# HOL-Dash_1_2.net
KiCad netlist of a schematic drawn in Altium Designer
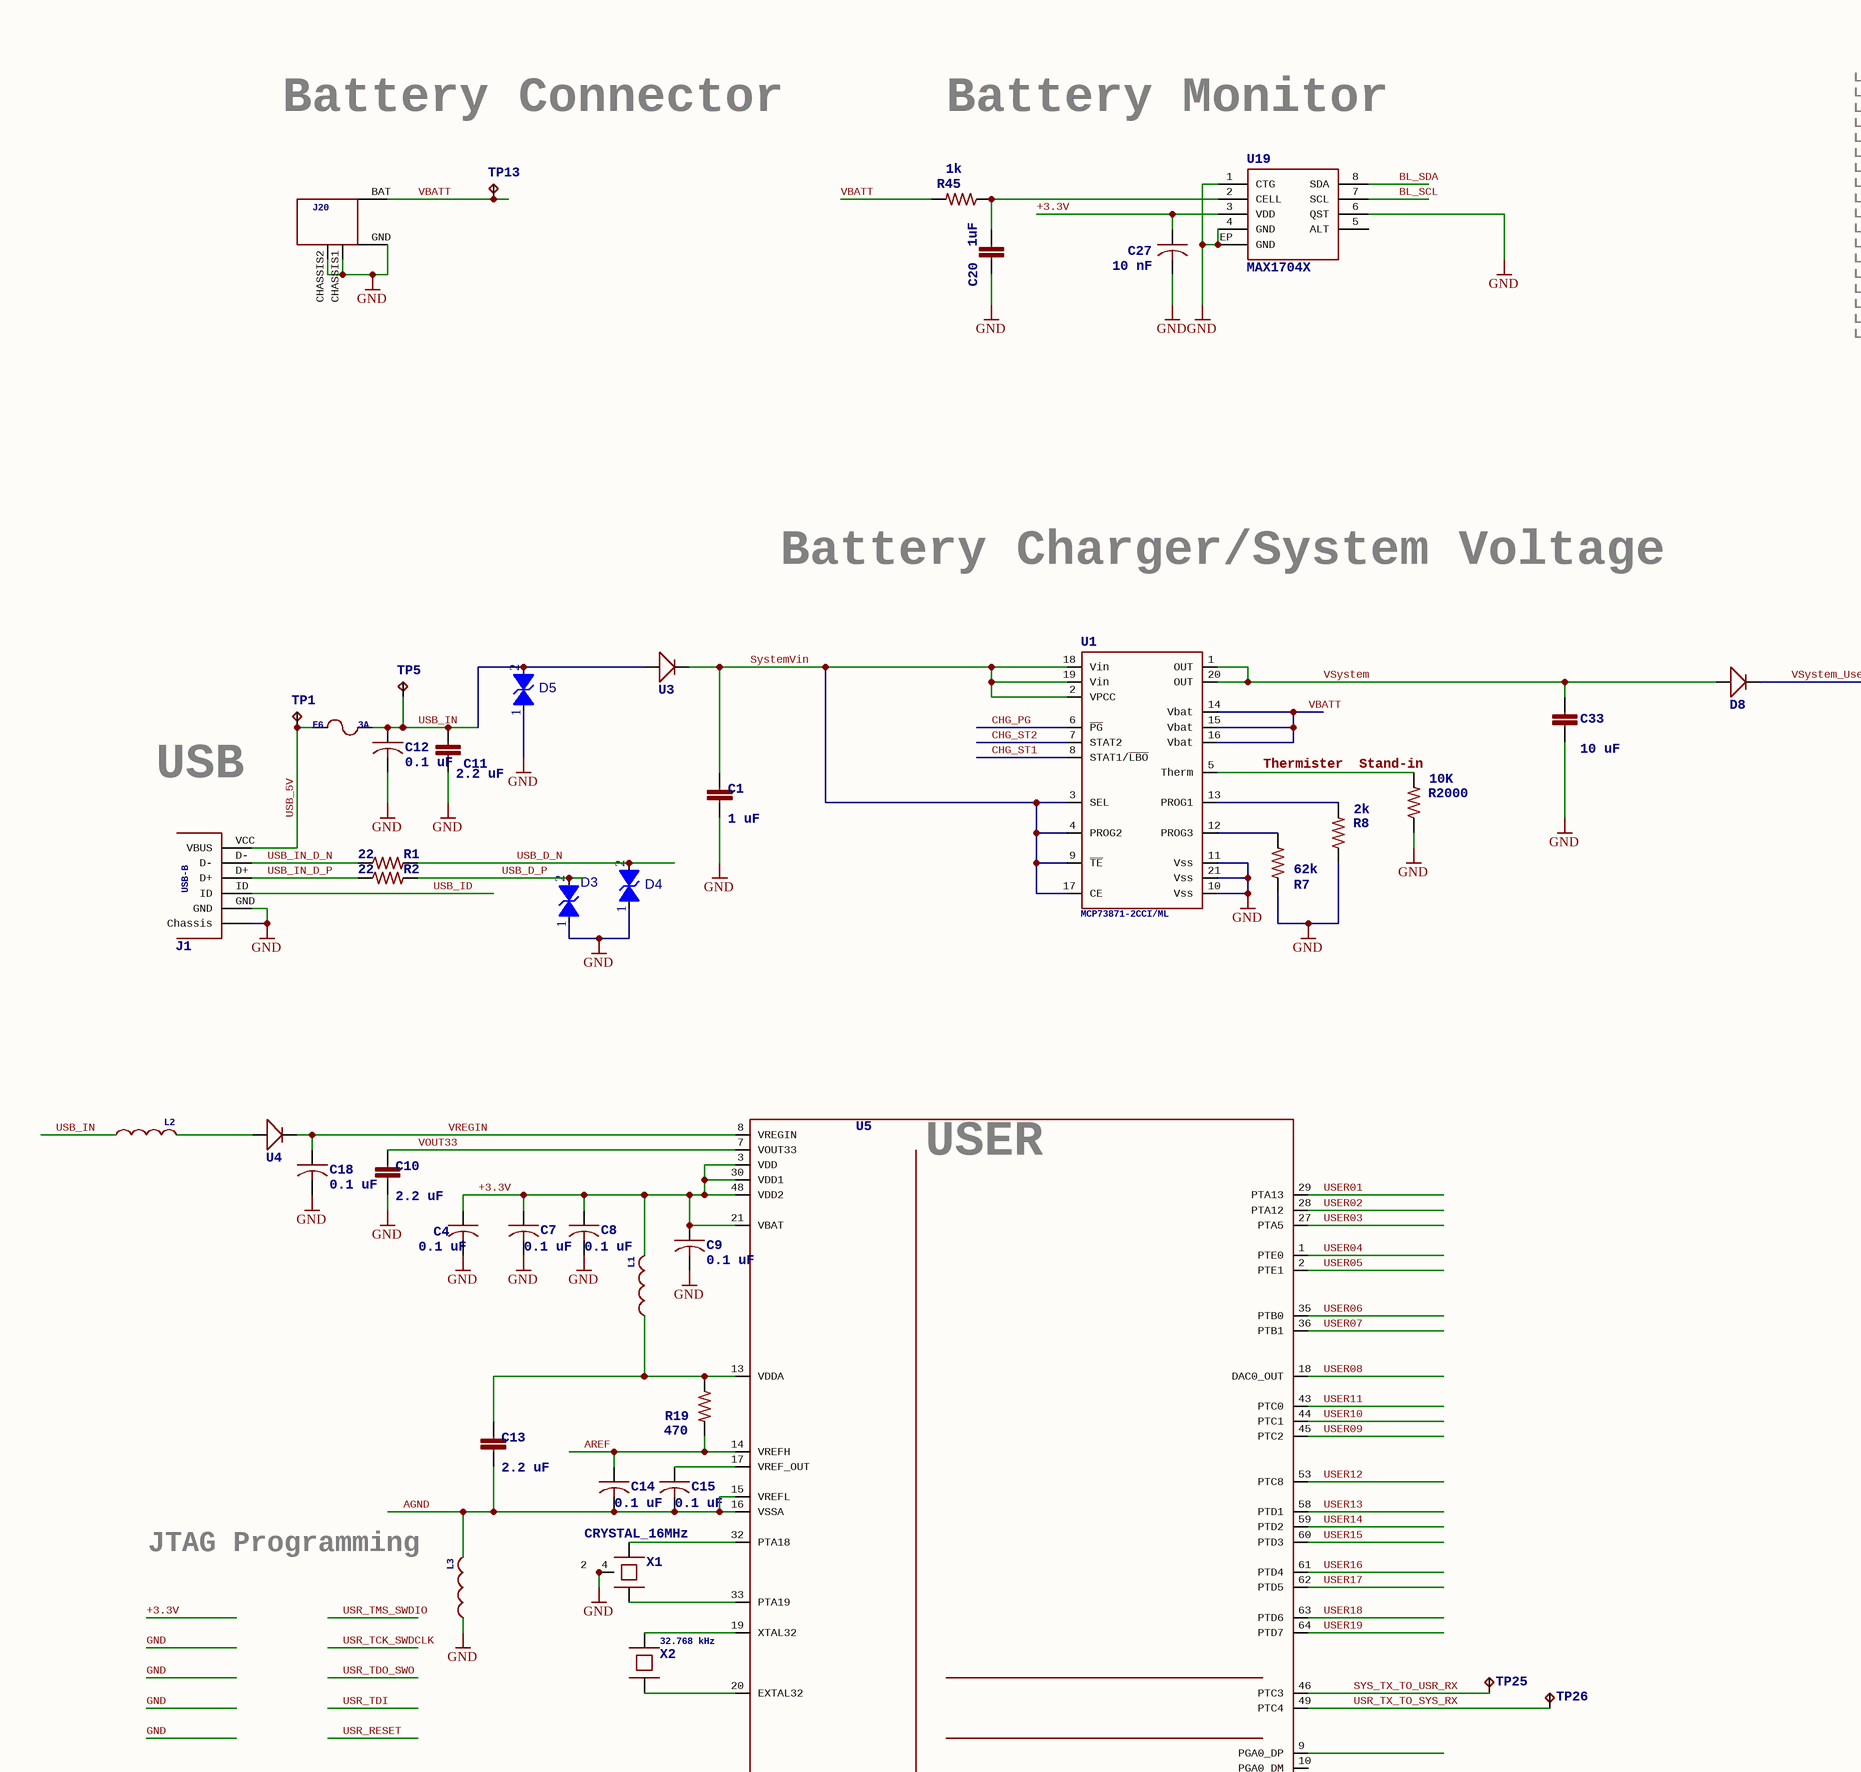
[diagram p0: HOL-Dash_1_2.SchDoc, top left]
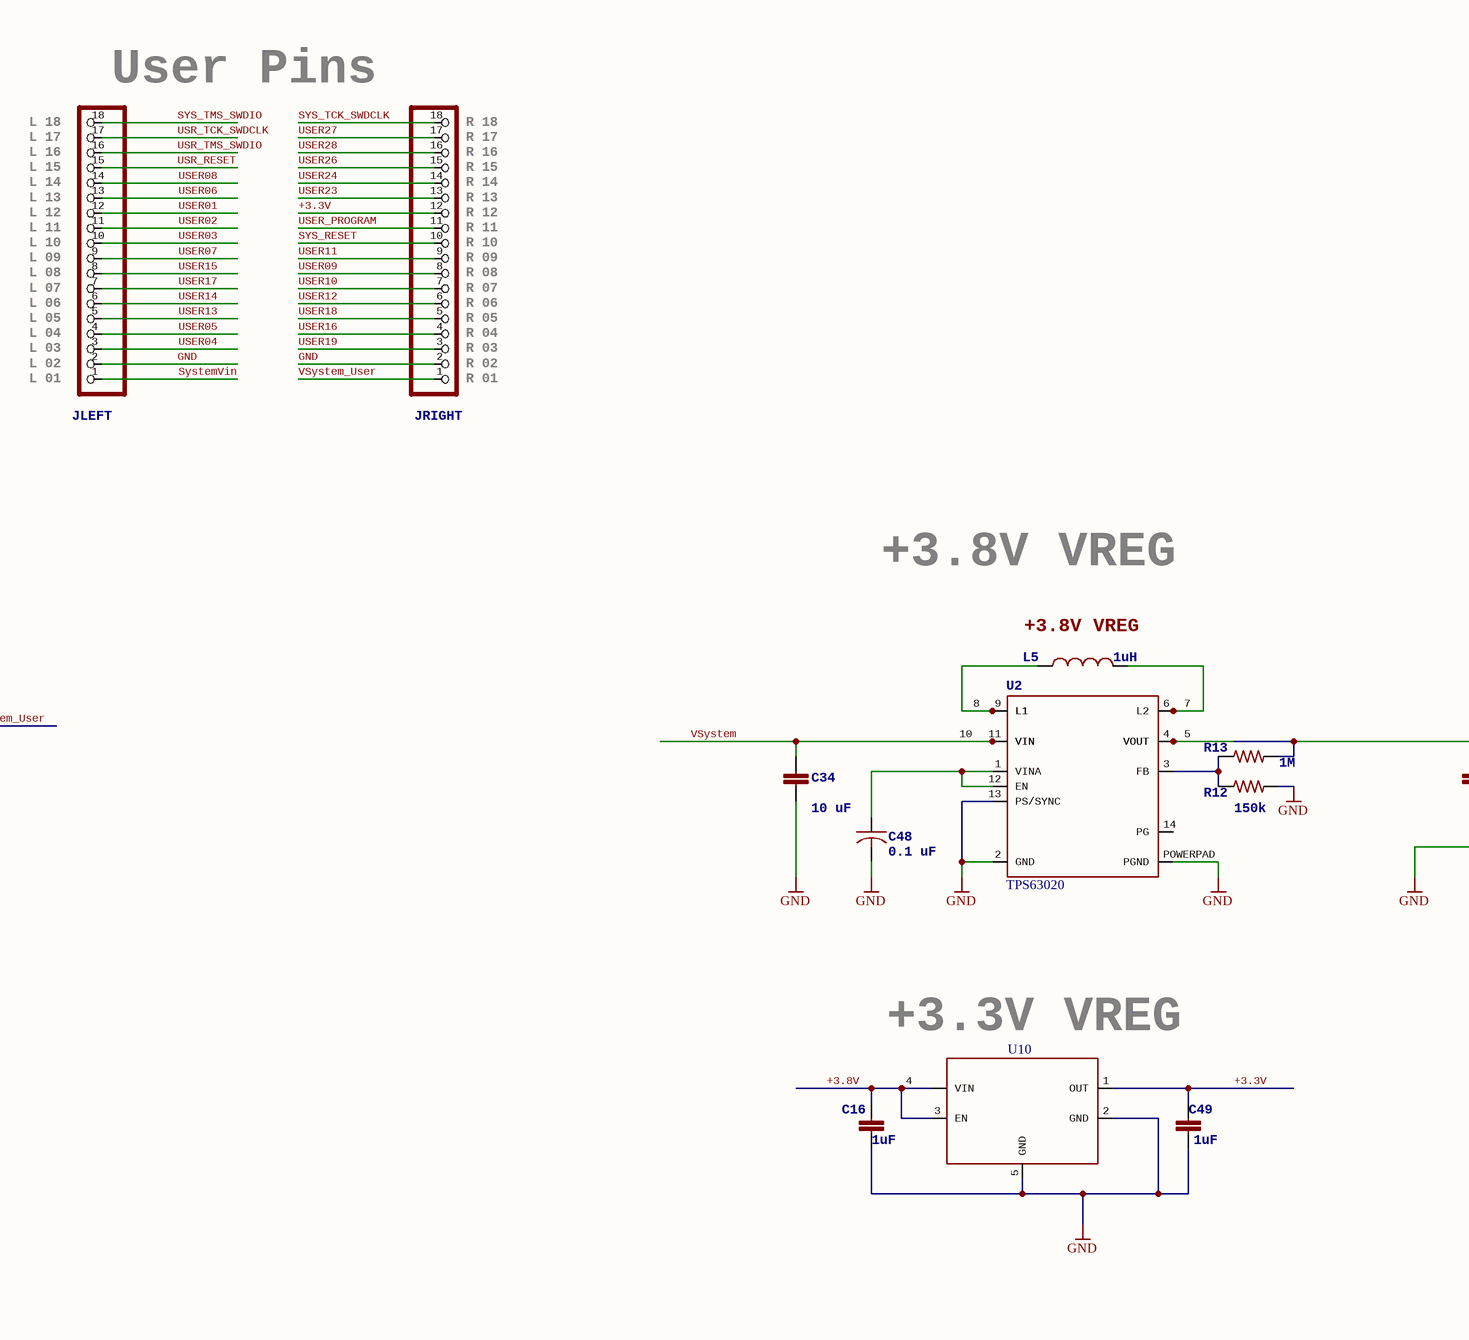
[diagram p1: HOL-Dash_1_2.SchDoc, top middle]
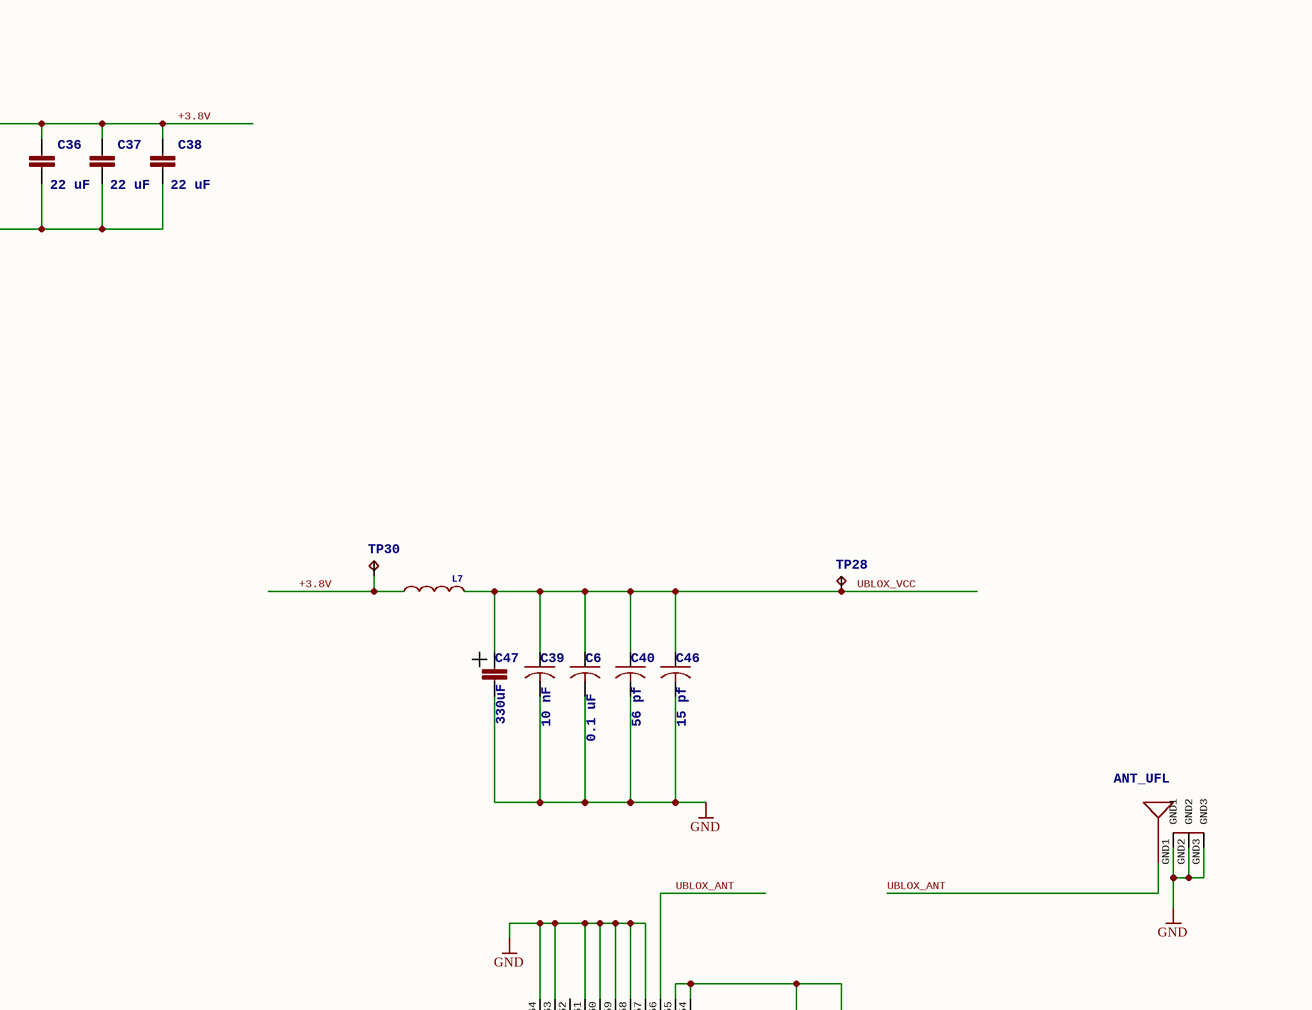
[diagram p2: HOL-Dash_1_2.SchDoc, top right]
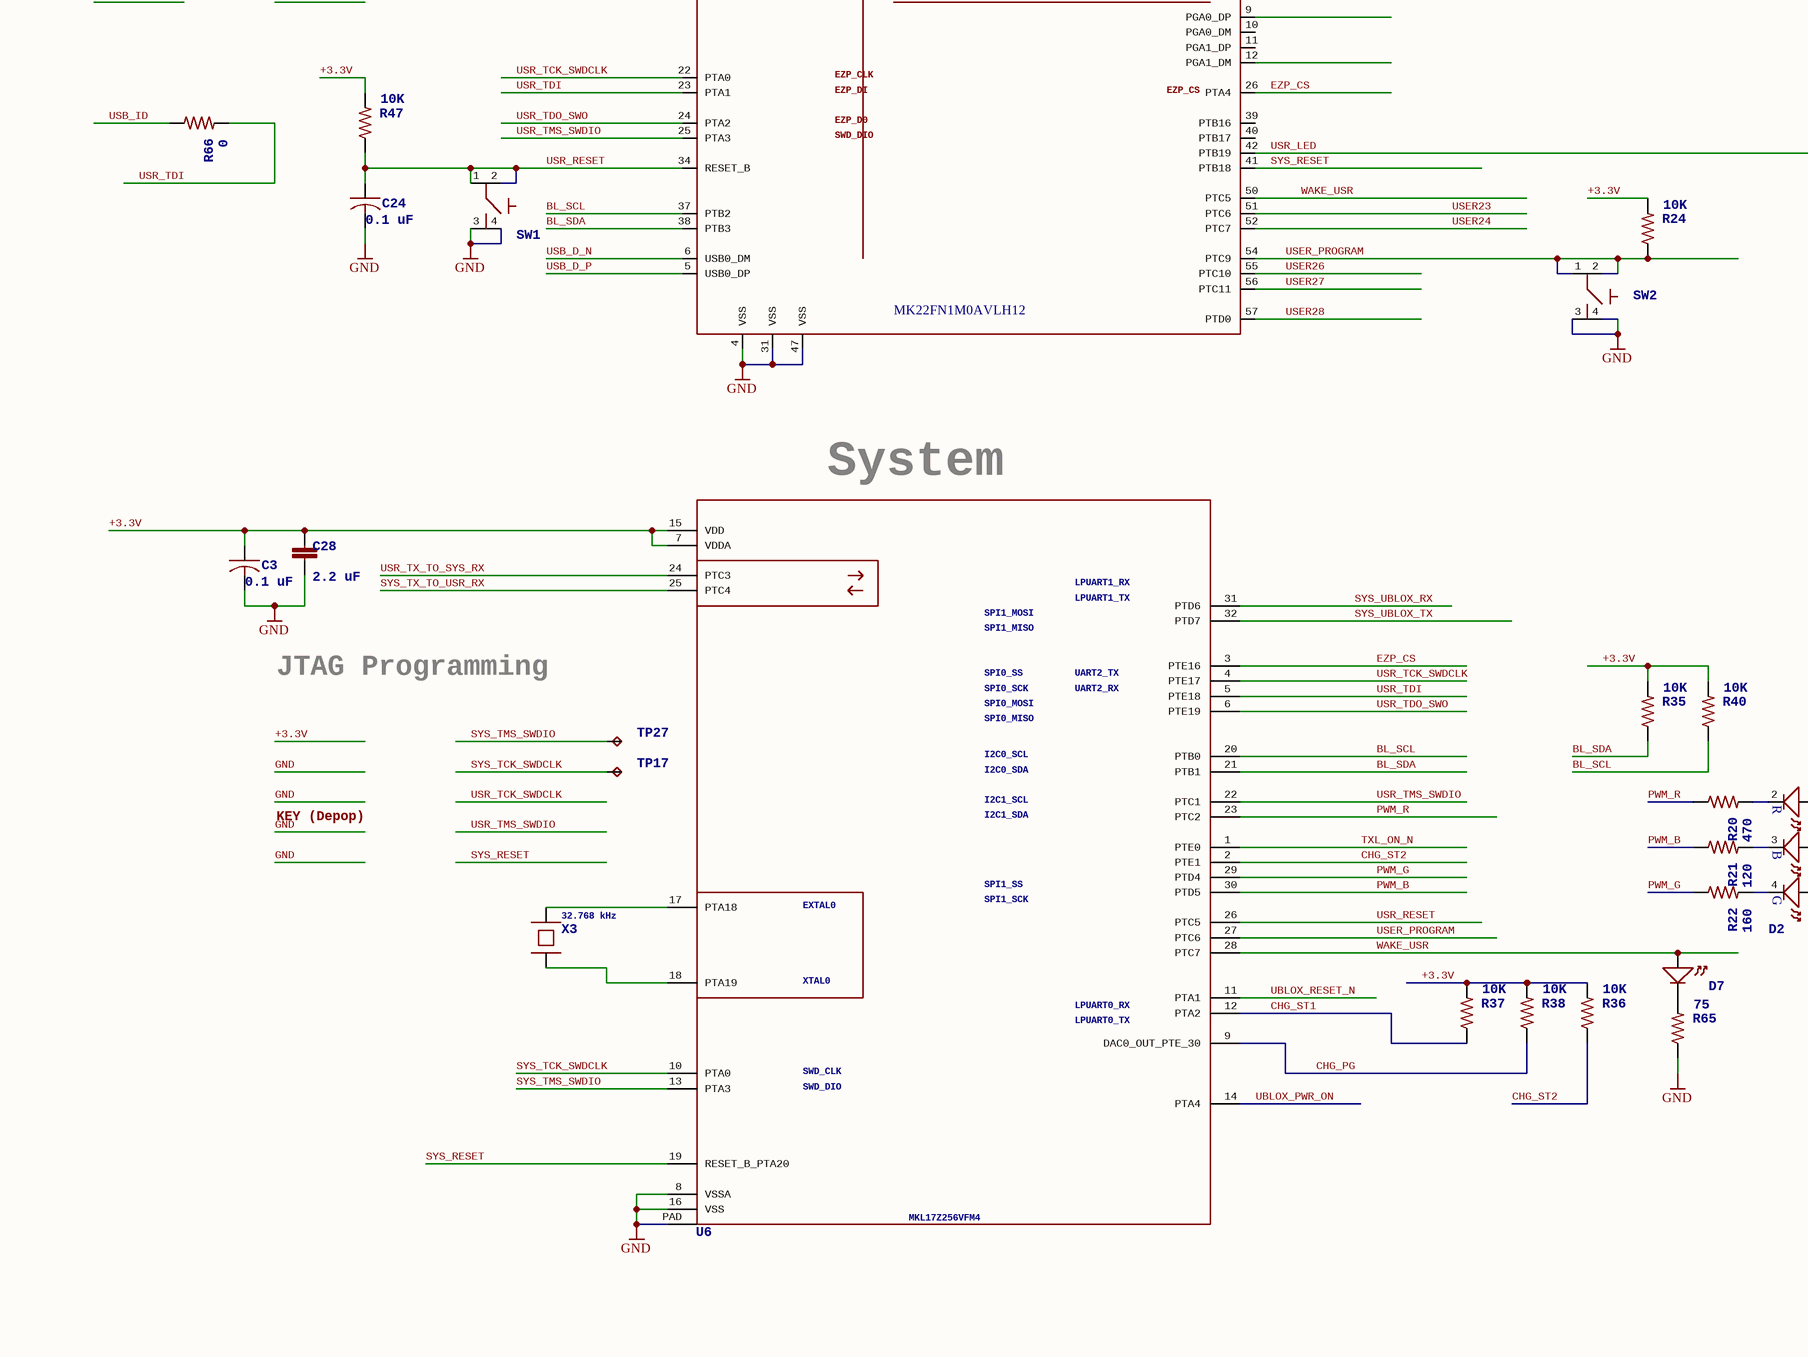
[diagram p3: HOL-Dash_1_2.SchDoc, bottom left]
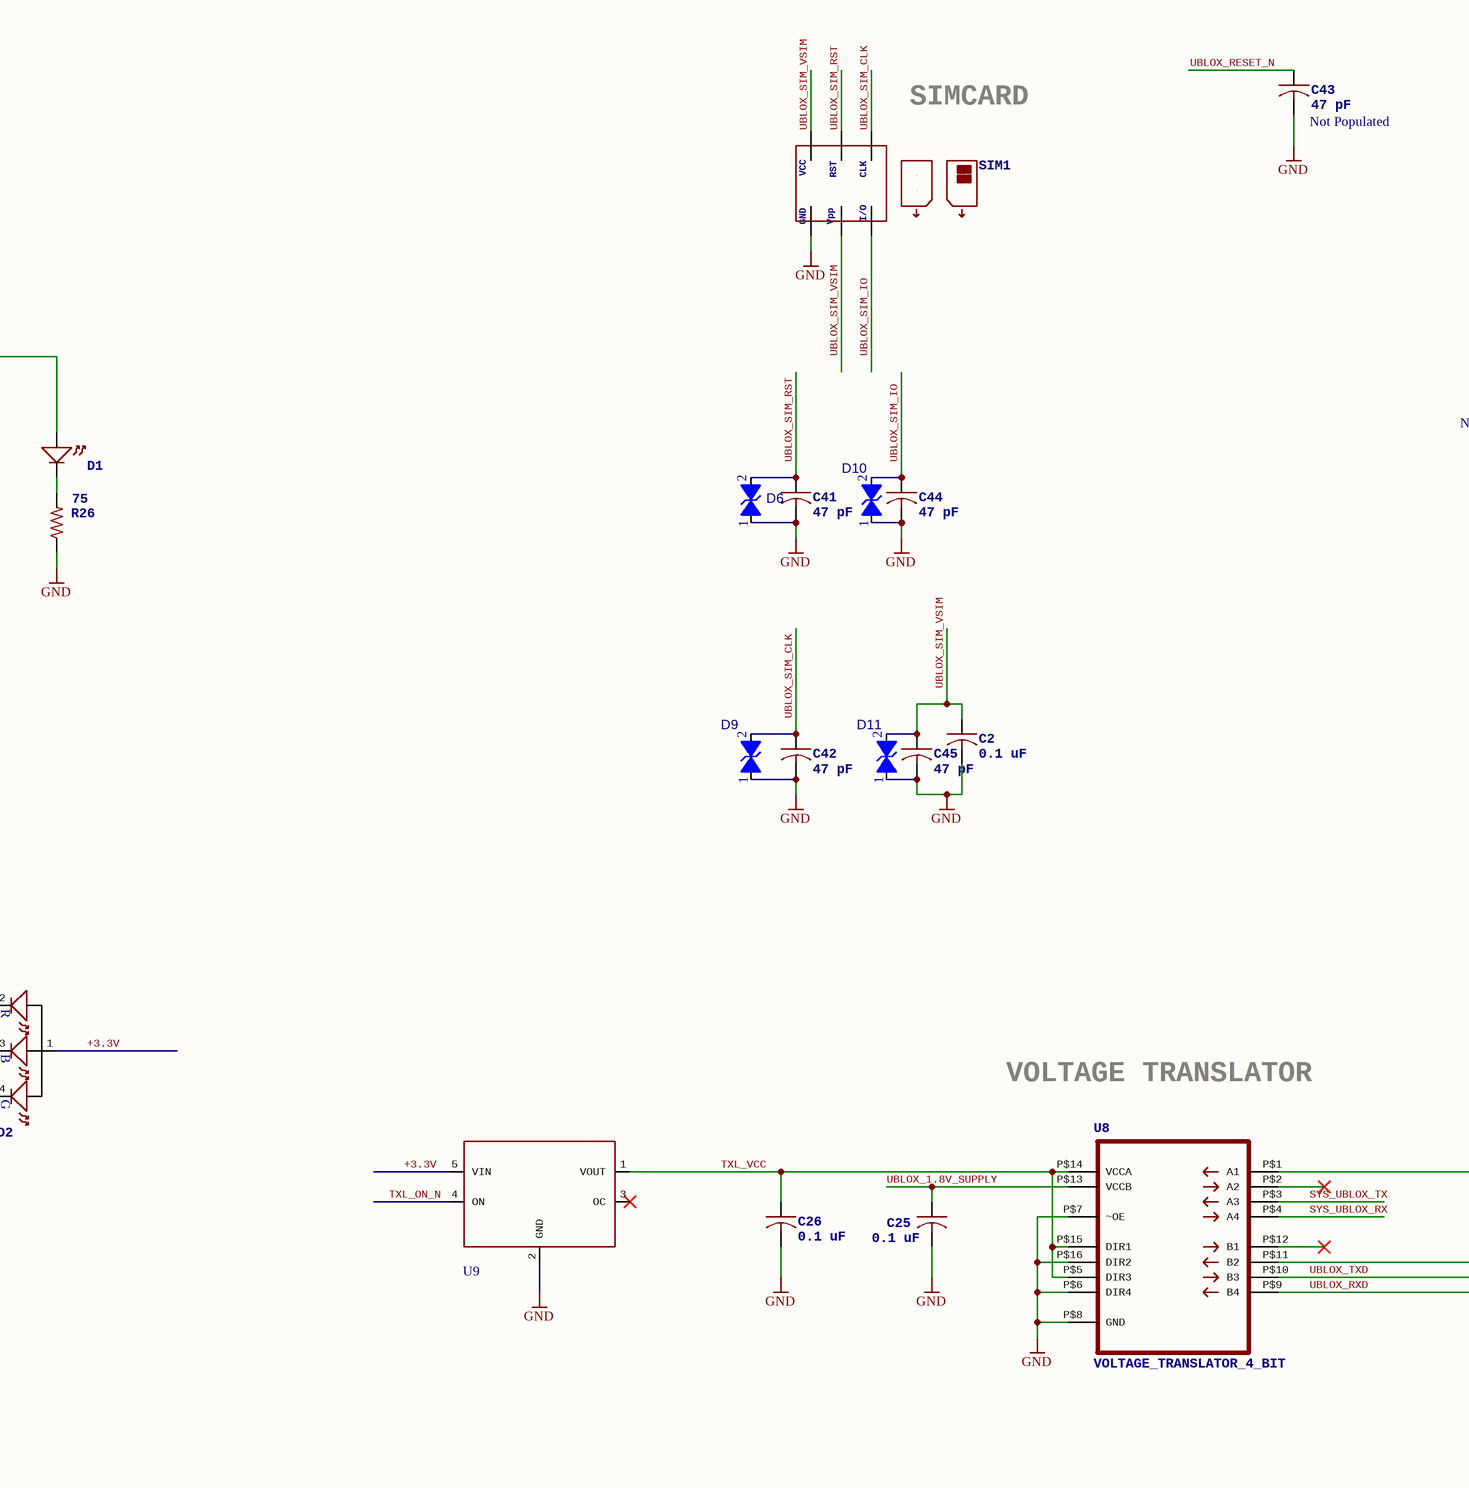
[diagram p4: HOL-Dash_1_2.SchDoc, bottom middle]
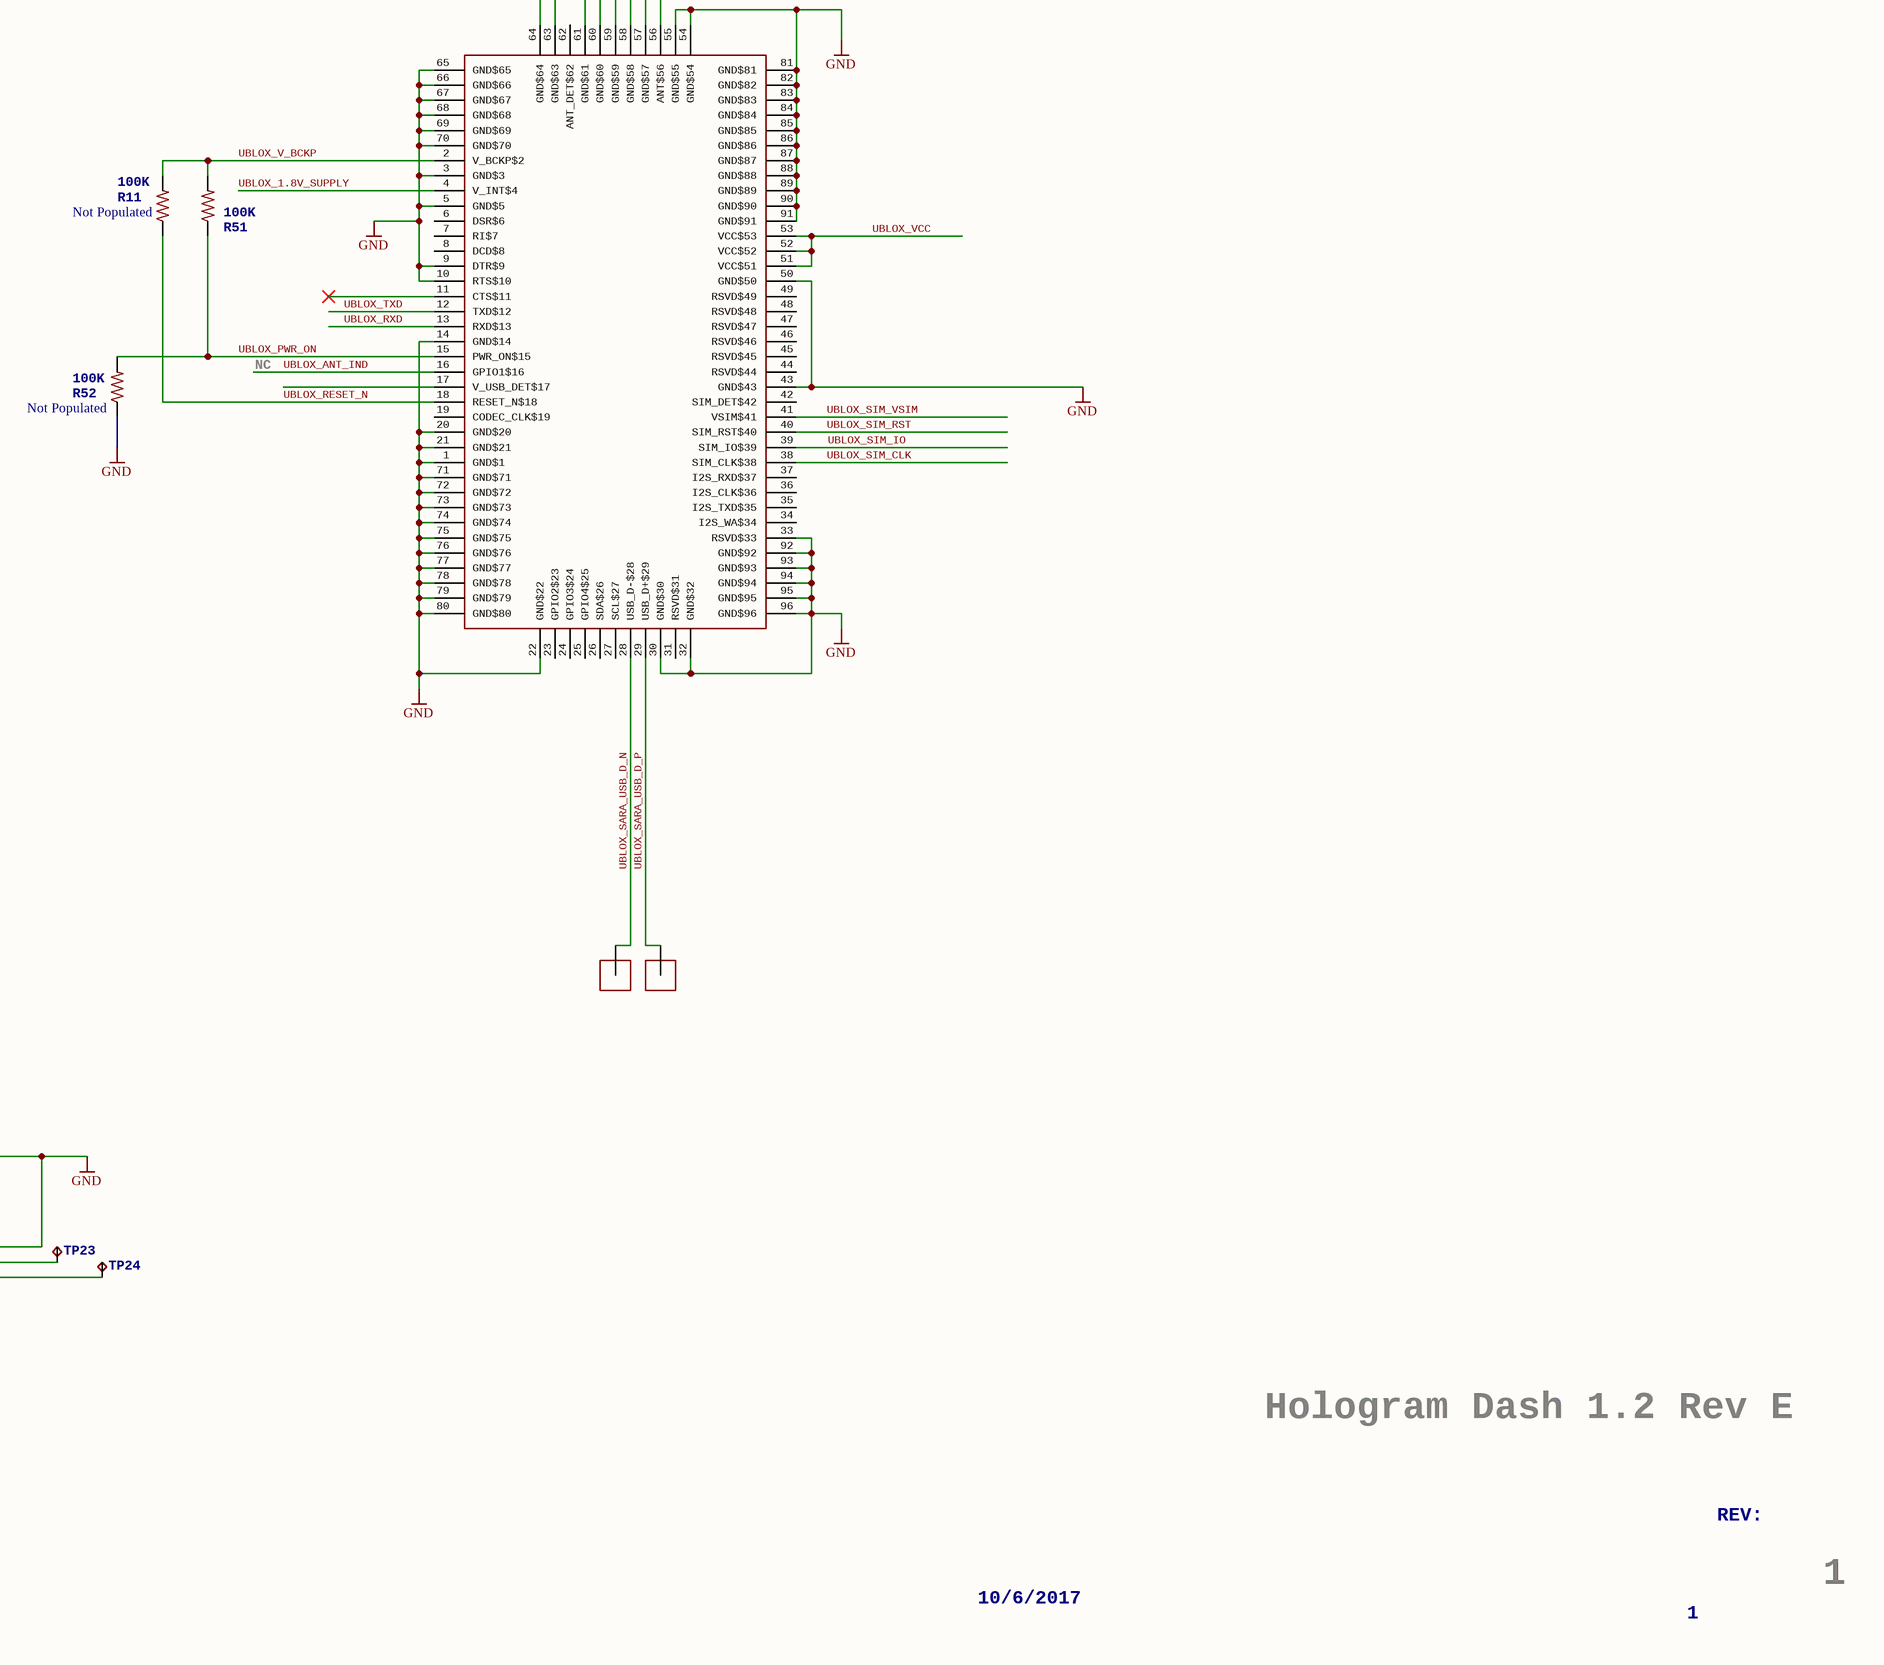
[diagram p5: HOL-Dash_1_2.SchDoc, bottom right]

(export (version "E")
  (design (tool "Eeschema 10.0.6"))
  (components
    (comp (ref "ANT_UFL")
      (value "ANT-A-1JB")
      (footprint "UFL")
      (description "Amphenol")
      (fields (field (name "MPN") "A-1JB"))
      (libsource (lib "KON-SU260") (part "ANT-A-1JB"))
    )
    (comp (ref "C1")
      (value "1 uF")
      (footprint "KON-SU260:CAP0603")
      (description "Capacitor, 1 uF, 0603")
      (fields (field (name "MPN") "GRM188R71C105KA12D") (field (name "MFG") "MURATA"))
      (libsource (lib "KON-SU260") (part "CAP1uF_0603"))
    )
    (comp (ref "C2")
      (value "0.1 uF")
      (footprint "KON-SU260:CAP0402")
      (description "CAPACITOR, 0.1 uF, 0402")
      (fields (field (name "MFG") "MURATA") (field (name "MPN") "GRM155R61C104KA88D"))
      (libsource (lib "KON-SU260") (part "CAP0.1uF_0402"))
    )
    (comp (ref "C3")
      (value "0.1 uF")
      (footprint "KON-SU260:CAP0402")
      (description "CAPACITOR, 0.1 uF, 0402")
      (fields (field (name "MFG") "MURATA") (field (name "MPN") "GRM155R61C104KA88D"))
      (libsource (lib "KON-SU260") (part "CAP0.1uF_0402"))
    )
    (comp (ref "C4")
      (value "0.1 uF")
      (footprint "KON-SU260:CAP0402")
      (description "CAPACITOR, 0.1 uF, 0402")
      (fields (field (name "MFG") "MURATA") (field (name "MPN") "GRM155R61C104KA88D"))
      (libsource (lib "KON-SU260") (part "CAP0.1uF_0402"))
    )
    (comp (ref "C6")
      (value "0.1 uF")
      (footprint "KON-SU260:CAP0402")
      (description "CAPACITOR, 0.1 uF, 0402")
      (fields (field (name "MFG") "MURATA") (field (name "MPN") "GRM155R61C104KA88D"))
      (libsource (lib "KON-SU260") (part "CAP0.1uF_0402"))
    )
    (comp (ref "C7")
      (value "0.1 uF")
      (footprint "KON-SU260:CAP0402")
      (description "CAPACITOR, 0.1 uF, 0402")
      (fields (field (name "MFG") "MURATA") (field (name "MPN") "GRM155R61C104KA88D"))
      (libsource (lib "KON-SU260") (part "CAP0.1uF_0402"))
    )
    (comp (ref "C8")
      (value "0.1 uF")
      (footprint "KON-SU260:CAP0402")
      (description "CAPACITOR, 0.1 uF, 0402")
      (fields (field (name "MFG") "MURATA") (field (name "MPN") "GRM155R61C104KA88D"))
      (libsource (lib "KON-SU260") (part "CAP0.1uF_0402"))
    )
    (comp (ref "C9")
      (value "0.1 uF")
      (footprint "KON-SU260:CAP0402")
      (description "CAPACITOR, 0.1 uF, 0402")
      (fields (field (name "MFG") "MURATA") (field (name "MPN") "GRM155R61C104KA88D"))
      (libsource (lib "KON-SU260") (part "CAP0.1uF_0402"))
    )
    (comp (ref "C10")
      (value "2.2 uF")
      (footprint "KON-SU260:CAP0603")
      (description "Capacitor, 2.2 uF, 0603")
      (fields (field (name "MPN") "CL10A225MQ8NNNC") (field (name "MFG") "SAMSUNG"))
      (libsource (lib "KON-SU260") (part "CAP2.2uF_0603"))
    )
    (comp (ref "C11")
      (value "2.2 uF")
      (footprint "KON-SU260:CAP0603")
      (description "Capacitor, 2.2 uF, 0603")
      (fields (field (name "MPN") "CL10A225MQ8NNNC") (field (name "MFG") "SAMSUNG"))
      (libsource (lib "KON-SU260") (part "CAP2.2uF_0603"))
    )
    (comp (ref "C12")
      (value "0.1 uF")
      (footprint "KON-SU260:CAP0402")
      (description "CAPACITOR, 0.1 uF, 0402")
      (fields (field (name "MFG") "MURATA") (field (name "MPN") "GRM155R61C104KA88D"))
      (libsource (lib "KON-SU260") (part "CAP0.1uF_0402"))
    )
    (comp (ref "C13")
      (value "2.2 uF")
      (footprint "KON-SU260:CAP0603")
      (description "Capacitor, 2.2 uF, 0603")
      (fields (field (name "MPN") "CL10A225MQ8NNNC") (field (name "MFG") "SAMSUNG"))
      (libsource (lib "KON-SU260") (part "CAP2.2uF_0603"))
    )
    (comp (ref "C14")
      (value "0.1 uF")
      (footprint "KON-SU260:CAP0402")
      (description "CAPACITOR, 0.1 uF, 0402")
      (fields (field (name "MFG") "MURATA") (field (name "MPN") "GRM155R61C104KA88D"))
      (libsource (lib "KON-SU260") (part "CAP0.1uF_0402"))
    )
    (comp (ref "C15")
      (value "0.1 uF")
      (footprint "KON-SU260:CAP0402")
      (description "CAPACITOR, 0.1 uF, 0402")
      (fields (field (name "MFG") "MURATA") (field (name "MPN") "GRM155R61C104KA88D"))
      (libsource (lib "KON-SU260") (part "CAP0.1uF_0402"))
    )
    (comp (ref "C16")
      (value "1uF")
      (footprint "KON-SU260:CAP0402")
      (description "CAPACITOR, 1uF, 0402")
      (fields (field (name "MPN") "04026D105KAT2A") (field (name "MFG") "AVX"))
      (libsource (lib "KON-SU260") (part "CAP1uF_0402"))
    )
    (comp (ref "C18")
      (value "0.1 uF")
      (footprint "KON-SU260:CAP0402")
      (description "CAPACITOR, 0.1 uF, 0402")
      (fields (field (name "MFG") "MURATA") (field (name "MPN") "GRM155R61C104KA88D"))
      (libsource (lib "KON-SU260") (part "CAP0.1uF_0402"))
    )
    (comp (ref "C20")
      (value "1uF")
      (footprint "KON-SU260:CAP0402")
      (description "CAPACITOR, 1uF, 0402")
      (fields (field (name "MPN") "04026D105KAT2A") (field (name "MFG") "AVX"))
      (libsource (lib "KON-SU260") (part "CAP1uF_0402"))
    )
    (comp (ref "C24")
      (value "0.1 uF")
      (footprint "KON-SU260:CAP0402")
      (description "CAPACITOR, 0.1 uF, 0402")
      (fields (field (name "MFG") "MURATA") (field (name "MPN") "GRM155R61C104KA88D"))
      (libsource (lib "KON-SU260") (part "CAP0.1uF_0402"))
    )
    (comp (ref "C25")
      (value "0.1 uF")
      (footprint "KON-SU260:CAP0402")
      (description "CAPACITOR, 0.1 uF, 0402")
      (fields (field (name "MFG") "MURATA") (field (name "MPN") "GRM155R61C104KA88D"))
      (libsource (lib "KON-SU260") (part "CAP0.1uF_0402"))
    )
    (comp (ref "C26")
      (value "0.1 uF")
      (footprint "KON-SU260:CAP0402")
      (description "CAPACITOR, 0.1 uF, 0402")
      (fields (field (name "MFG") "MURATA") (field (name "MPN") "GRM155R61C104KA88D"))
      (libsource (lib "KON-SU260") (part "CAP0.1uF_0402"))
    )
    (comp (ref "C27")
      (value "10 nF")
      (footprint "KON-SU260:CAP0402")
      (description "CAPACITOR, 10 nF, 0402")
      (fields (field (name "MFG") "MURATA") (field (name "MPN") "GRM155R71C103KA01D"))
      (libsource (lib "KON-SU260") (part "CAP10nF_0402"))
    )
    (comp (ref "C28")
      (value "2.2 uF")
      (footprint "KON-SU260:CAP0603")
      (description "Capacitor, 2.2 uF, 0603")
      (fields (field (name "MPN") "CL10A225MQ8NNNC") (field (name "MFG") "SAMSUNG"))
      (libsource (lib "KON-SU260") (part "CAP2.2uF_0603"))
    )
    (comp (ref "C33")
      (value "10 uF")
      (footprint "KON-SU260:CAP0603")
      (description "Capacitor, 10 uF, 0603")
      (fields (field (name "MPN") "GRM188R60J106ME84D") (field (name "MFG") "Murata"))
      (libsource (lib "KON-SU260") (part "CAP10uF_0603"))
    )
    (comp (ref "C34")
      (value "10 uF")
      (footprint "KON-SU260:CAP0603")
      (description "Capacitor, 10 uF, 0603")
      (fields (field (name "MPN") "GRM188R60J106ME84D") (field (name "MFG") "Murata"))
      (libsource (lib "KON-SU260") (part "CAP10uF_0603"))
    )
    (comp (ref "C36")
      (value "22 uF")
      (footprint "KON-SU260:CAP0603")
      (description "Capacitor, 22 uF, 0603")
      (fields (field (name "MPN") "GRM188R60J226MEA0D") (field (name "MFG") "MURATA"))
      (libsource (lib "KON-SU260") (part "CAP22uF_0603"))
    )
    (comp (ref "C37")
      (value "22 uF")
      (footprint "KON-SU260:CAP0603")
      (description "Capacitor, 22 uF, 0603")
      (fields (field (name "MPN") "GRM188R60J226MEA0D") (field (name "MFG") "MURATA"))
      (libsource (lib "KON-SU260") (part "CAP22uF_0603"))
    )
    (comp (ref "C38")
      (value "22 uF")
      (footprint "KON-SU260:CAP0603")
      (description "Capacitor, 22 uF, 0603")
      (fields (field (name "MPN") "GRM188R60J226MEA0D") (field (name "MFG") "MURATA"))
      (libsource (lib "KON-SU260") (part "CAP22uF_0603"))
    )
    (comp (ref "C39")
      (value "10 nF")
      (footprint "KON-SU260:CAP0402")
      (description "CAPACITOR, 10 nF, 0402")
      (fields (field (name "MFG") "MURATA") (field (name "MPN") "GRM155R71C103KA01D"))
      (libsource (lib "KON-SU260") (part "CAP10nF_0402"))
    )
    (comp (ref "C40")
      (value "56 pf")
      (footprint "KON-SU260:CAP0402")
      (description "CAPACITOR, 56 pF, 0402")
      (fields (field (name "MFG") "KEMET") (field (name "MPN") "C0402C560J5GACTU"))
      (libsource (lib "KON-SU260") (part "CAP56pF_0402"))
    )
    (comp (ref "C41")
      (value "47 pF")
      (footprint "KON-SU260:CAP0402")
      (description "CAPACITOR, 47 pF, 0402")
      (fields (field (name "MFG") "AVX") (field (name "MPN") "04025A470JAT2A"))
      (libsource (lib "KON-SU260") (part "CAP47pf_0402"))
    )
    (comp (ref "C42")
      (value "47 pF")
      (footprint "KON-SU260:CAP0402")
      (description "CAPACITOR, 47 pF, 0402")
      (fields (field (name "MFG") "AVX") (field (name "MPN") "04025A470JAT2A"))
      (libsource (lib "KON-SU260") (part "CAP47pf_0402"))
    )
    (comp (ref "C43")
      (value "47 pF")
      (footprint "KON-SU260:CAP0402")
      (description "CAPACITOR, 47 pF, 0402")
      (fields
        (field (name "MFG") "AVX")
        (field (name "MPN") "04025A470JAT2A")
        (field (name "NP") "Not Populated")
      )
      (libsource (lib "KON-SU260") (part "CAP47pf_0402"))
    )
    (comp (ref "C44")
      (value "47 pF")
      (footprint "KON-SU260:CAP0402")
      (description "CAPACITOR, 47 pF, 0402")
      (fields (field (name "MFG") "AVX") (field (name "MPN") "04025A470JAT2A"))
      (libsource (lib "KON-SU260") (part "CAP47pf_0402"))
    )
    (comp (ref "C45")
      (value "47 pF")
      (footprint "KON-SU260:CAP0402")
      (description "CAPACITOR, 47 pF, 0402")
      (fields (field (name "MFG") "AVX") (field (name "MPN") "04025A470JAT2A"))
      (libsource (lib "KON-SU260") (part "CAP47pf_0402"))
    )
    (comp (ref "C46")
      (value "15 pf")
      (footprint "KON-SU260:CAP0402")
      (description "CAPACITOR, 15 pF, 0402")
      (fields (field (name "MFG") "AVX/ELCO") (field (name "MPN") "04025A150JAT2A"))
      (libsource (lib "KON-SU260") (part "CAP15pF_0402"))
    )
    (comp (ref "C47")
      (value "330uF")
      (footprint "KON-SU260:CAP1210POL")
      (description "Capacitor, 330 uF, 1210, Polarized Tantalum")
      (fields (field (name "MPN") "F950J337MBAAQ2") (field (name "MFG") "AVX"))
      (libsource (lib "KON-SU260") (part "CAP330uF_1210P"))
    )
    (comp (ref "C48")
      (value "0.1 uF")
      (footprint "KON-SU260:CAP0402")
      (description "CAPACITOR, 0.1 uF, 0402")
      (fields (field (name "MFG") "MURATA") (field (name "MPN") "GRM155R61C104KA88D"))
      (libsource (lib "KON-SU260") (part "CAP0.1uF_0402"))
    )
    (comp (ref "C49")
      (value "1uF")
      (footprint "KON-SU260:CAP0402")
      (description "CAPACITOR, 1uF, 0402")
      (fields (field (name "MPN") "04026D105KAT2A") (field (name "MFG") "AVX"))
      (libsource (lib "KON-SU260") (part "CAP1uF_0402"))
    )
    (comp (ref "D1")
      (value "LED_0402_VLMW")
      (footprint "LED_0402_VISHAY_VLMW")
      (description "LED, Vishay White 0402")
      (fields (field (name "MFG") "VISHAY") (field (name "MPN") "VLMW1500-GS08"))
      (libsource (lib "KON-SU260") (part "LED_0402_VLMW"))
    )
    (comp (ref "D2")
      (value "LED_RGB_1mm_sq")
      (footprint "LED-RGB-1X1")
      (description "LED, Tri-color, RGB, 1mm sq")
      (fields (field (name "MFG") "Rohm") (field (name "MPN") "SMLP34RGB2W3"))
      (libsource (lib "KON-SU260") (part "LED_RGB_1mm_sq"))
    )
    (comp (ref "D3")
      (value "~")
      (footprint "PESD_0402")
      (description "DIODE,ZENER VOLTAGE SUPPRESSOR,+/-14V")
      (fields (field (name "MFG") "Littlefuse") (field (name "MPN") "PESD0402-140"))
      (libsource (lib "KON-SU260") (part "PESD_14V"))
    )
    (comp (ref "D4")
      (value "~")
      (footprint "PESD_0402")
      (description "DIODE,ZENER VOLTAGE SUPPRESSOR,+/-14V")
      (fields (field (name "MFG") "Littlefuse") (field (name "MPN") "PESD0402-140"))
      (libsource (lib "KON-SU260") (part "PESD_14V"))
    )
    (comp (ref "D5")
      (value "~")
      (footprint "PESD_0402")
      (description "DIODE,ZENER VOLTAGE SUPPRESSOR,+/-14V")
      (fields (field (name "MFG") "Littlefuse") (field (name "MPN") "PESD0402-140"))
      (libsource (lib "KON-SU260") (part "PESD_14V"))
    )
    (comp (ref "D6")
      (value "~")
      (footprint "PESD_0402")
      (description "DIODE,ZENER VOLTAGE SUPPRESSOR,+/-14V")
      (fields (field (name "MFG") "Littlefuse") (field (name "MPN") "PESD0402-140"))
      (libsource (lib "KON-SU260") (part "PESD_14V"))
    )
    (comp (ref "D7")
      (value "LED_0402_VLMW")
      (footprint "LED_0402_VISHAY_VLMW")
      (description "LED, Vishay White 0402")
      (fields (field (name "MFG") "VISHAY") (field (name "MPN") "VLMW1500-GS08"))
      (libsource (lib "KON-SU260") (part "LED_0402_VLMW"))
    )
    (comp (ref "D8")
      (value "CDBQR0230L")
      (footprint "DIODE_0402")
      (description "Schottky Barrier Diode, 200 mA, 30 V, 0402 package")
      (fields (field (name "MFG") "Comchip"))
      (libsource (lib "KON-SU260") (part "DIODE_0402_200mA"))
    )
    (comp (ref "D9")
      (value "~")
      (footprint "PESD_0402")
      (description "DIODE,ZENER VOLTAGE SUPPRESSOR,+/-14V")
      (fields (field (name "MFG") "Littlefuse") (field (name "MPN") "PESD0402-140"))
      (libsource (lib "KON-SU260") (part "PESD_14V"))
    )
    (comp (ref "D10")
      (value "~")
      (footprint "PESD_0402")
      (description "DIODE,ZENER VOLTAGE SUPPRESSOR,+/-14V")
      (fields (field (name "MFG") "Littlefuse") (field (name "MPN") "PESD0402-140"))
      (libsource (lib "KON-SU260") (part "PESD_14V"))
    )
    (comp (ref "D11")
      (value "~")
      (footprint "PESD_0402")
      (description "DIODE,ZENER VOLTAGE SUPPRESSOR,+/-14V")
      (fields (field (name "MFG") "Littlefuse") (field (name "MPN") "PESD0402-140"))
      (libsource (lib "KON-SU260") (part "PESD_14V"))
    )
    (comp (ref "F6")
      (value "3A")
      (footprint "KON-SU260:RES0603")
      (description "Fuse, 3A, 0603")
      (fields (field (name "MFG") "Bourns") (field (name "MPN") "SF-0603S300-2"))
      (libsource (lib "KON-SU260") (part "FUSE_0603"))
    )
    (comp (ref "J1")
      (value "Micro USB B FCI 10118193")
      (footprint "USB_MICRO_FCI_10118193")
      (description "Connector, Micro USB B, FCI")
      (fields
        (field (name "MFG") "Amphenol FCI")
        (field (name "MPN") "10118193-0001LF")
        (field (name "USB-B") "USB-B")
      )
      (libsource (lib "KON-SU260") (part "USB_MICRO_B_FCI_10118193"))
    )
    (comp (ref "J20")
      (value "BAT_TERM_TOP_ENTRY")
      (footprint "JST-PH-2-Top")
      (description "Battery Connector JST-PH2 Top Entry")
      (fields (field (name "MPN") "B2B-PH-SM4-TB(LF)(SN)") (field (name "MFG") "JST"))
      (libsource (lib "KON-SU260") (part "BAT_TERM_TOP_ENTRY"))
    )
    (comp (ref "JLEFT")
      (value "22-28-4180")
      (footprint "KON-SU260:1X18")
      (description "Header, Male, 1x18, 0.1\"")
      (fields (field (name "MFG") "MOLEX"))
      (libsource (lib "KON-SU260") (part "PINHD-1X18"))
    )
    (comp (ref "JRIGHT")
      (value "22-28-4180")
      (footprint "KON-SU260:1X18")
      (description "Header, Male, 1x18, 0.1\"")
      (fields (field (name "MFG") "MOLEX"))
      (libsource (lib "KON-SU260") (part "PINHD-1X18"))
    )
    (comp (ref "L1")
      (value "FerriteBead_220ohm")
      (footprint "KON-SU260:RES0603")
      (description "FerriteBead, 220ohm")
      (fields (field (name "MPN") "BLM18AG121SN1D") (field (name "MFG") "Murata"))
      (libsource (lib "KON-SU260") (part "FerriteBead_220ohm"))
    )
    (comp (ref "L2")
      (value "FerriteBead_220ohm")
      (footprint "KON-SU260:RES0603")
      (description "FerriteBead, 220ohm")
      (fields (field (name "MPN") "BLM18AG121SN1D") (field (name "MFG") "Murata"))
      (libsource (lib "KON-SU260") (part "FerriteBead_220ohm"))
    )
    (comp (ref "L3")
      (value "FerriteBead_220ohm")
      (footprint "KON-SU260:RES0603")
      (description "FerriteBead, 220ohm")
      (fields (field (name "MPN") "BLM18AG121SN1D") (field (name "MFG") "Murata"))
      (libsource (lib "KON-SU260") (part "FerriteBead_220ohm"))
    )
    (comp (ref "L5")
      (value "1uH")
      (footprint "COILCRAFT_XFL4020")
      (description "Inductor, 1 uH, Coilcraft")
      (fields (field (name "MPN") "XFL4020-102MEC") (field (name "MFG") "Coilcraft"))
      (libsource (lib "KON-SU260") (part "INDUCTOR_1UH_XFL4020-102MEC"))
    )
    (comp (ref "L7")
      (value "FerriteBead_220ohm")
      (footprint "KON-SU260:RES0603")
      (description "FerriteBead, 220ohm")
      (fields (field (name "MPN") "BLM18AG121SN1D") (field (name "MFG") "Murata"))
      (libsource (lib "KON-SU260") (part "FerriteBead_220ohm"))
    )
    (comp (ref "R1")
      (value "22")
      (footprint "KON-SU260:RES0402")
      (description "Resistor, 22 ohm, 0402 case, 1%")
      (fields (field (name "MFG") "YAEGO") (field (name "MPN") "RC0402FR-0722RL"))
      (libsource (lib "KON-SU260") (part "RES22R_0402"))
    )
    (comp (ref "R2")
      (value "22")
      (footprint "KON-SU260:RES0402")
      (description "Resistor, 22 ohm, 0402 case, 1%")
      (fields (field (name "MFG") "YAEGO") (field (name "MPN") "RC0402FR-0722RL"))
      (libsource (lib "KON-SU260") (part "RES22R_0402"))
    )
    (comp (ref "R7")
      (value "62k")
      (footprint "KON-SU260:RES0402")
      (description "Resistor, 62K ohm, 0402 case")
      (fields (field (name "MFG") "YAEGO") (field (name "MPN") "RC0402FR-0762KL"))
      (libsource (lib "KON-SU260") (part "RES62K_0402_1"))
    )
    (comp (ref "R8")
      (value "2k")
      (footprint "KON-SU260:RES0402")
      (description "Resistor, 2K ohm, 0402 case")
      (fields (field (name "MFG") "YAEGO") (field (name "MPN") "RC0402FR-072KL"))
      (libsource (lib "KON-SU260") (part "RES2K_0402"))
    )
    (comp (ref "R11")
      (value "100K")
      (footprint "KON-SU260:RES0402")
      (description "Resistor, 100k ohm, 0402")
      (fields
        (field (name "MFG") "PANASONIC")
        (field (name "MPN") "ERJ-2GEJ104X")
        (field (name "NP") "Not Populated")
      )
      (libsource (lib "KON-SU260") (part "RES100K_0402"))
    )
    (comp (ref "R12")
      (value "150k")
      (footprint "KON-SU260:RES0402")
      (description "Res, 150k ohm, 0402 case, 1%")
      (fields (field (name "MFG") "YAEGO") (field (name "MPN") "RC0402FR-07150KL"))
      (libsource (lib "KON-SU260") (part "RES150K_0402"))
    )
    (comp (ref "R13")
      (value "1M")
      (footprint "KON-SU260:RES0402")
      (description "Resistor, 1M ohm, 0402 case, 1%")
      (fields (field (name "MFG") "YAEGO") (field (name "MPN") "RC0402FR-071ML"))
      (libsource (lib "KON-SU260") (part "RES1M_0402"))
    )
    (comp (ref "R19")
      (value "470")
      (footprint "KON-SU260:RES0402")
      (description "Resistor, 470 ohm, 0402 case, 1%")
      (fields (field (name "MFG") "PANASONIC") (field (name "MPN") "ERJ-2GEJ471X"))
      (libsource (lib "KON-SU260") (part "RES470R_0402"))
    )
    (comp (ref "R20")
      (value "470")
      (footprint "KON-SU260:RES0402")
      (description "Resistor, 470 ohm, 0402 case, 1%")
      (fields (field (name "MFG") "PANASONIC") (field (name "MPN") "ERJ-2GEJ471X"))
      (libsource (lib "KON-SU260") (part "RES470R_0402"))
    )
    (comp (ref "R21")
      (value "120")
      (footprint "KON-SU260:RES0402")
      (description "Resistor, 120 ohm, 0402 case, 1%")
      (fields (field (name "MFG") "PANASONIC") (field (name "MPN") "ERJ-2GEJ121X"))
      (libsource (lib "KON-SU260") (part "RES120R_0402"))
    )
    (comp (ref "R22")
      (value "160")
      (footprint "KON-SU260:RES0402")
      (description "Resistor, 160 ohm, 0402 case, 1%")
      (fields (field (name "MFG") "PANASONIC") (field (name "MPN") "ERJ-2GEJ161X"))
      (libsource (lib "KON-SU260") (part "RES160R_0402"))
    )
    (comp (ref "R24")
      (value "10K")
      (footprint "KON-SU260:RES0402")
      (description "Resistor, 10k ohm, 0402")
      (fields (field (name "MFG") "YAEGO") (field (name "MPN") "RC0402JR-0710KL"))
      (libsource (lib "KON-SU260") (part "RES10K_0402"))
    )
    (comp (ref "R26")
      (value "75")
      (footprint "KON-SU260:RES0402")
      (description "Resistor, 75 ohm, 0402, 1%")
      (fields (field (name "MFG") "YAEGO") (field (name "MPN") "RC0402FR-0775RL"))
      (libsource (lib "KON-SU260") (part "RES75R_0402"))
    )
    (comp (ref "R35")
      (value "10K")
      (footprint "KON-SU260:RES0402")
      (description "Resistor, 10k ohm, 0402")
      (fields (field (name "MFG") "YAEGO") (field (name "MPN") "RC0402JR-0710KL"))
      (libsource (lib "KON-SU260") (part "RES10K_0402"))
    )
    (comp (ref "R36")
      (value "10K")
      (footprint "KON-SU260:RES0402")
      (description "Resistor, 10k ohm, 0402")
      (fields (field (name "MFG") "YAEGO") (field (name "MPN") "RC0402JR-0710KL"))
      (libsource (lib "KON-SU260") (part "RES10K_0402"))
    )
    (comp (ref "R37")
      (value "10K")
      (footprint "KON-SU260:RES0402")
      (description "Resistor, 10k ohm, 0402")
      (fields (field (name "MFG") "YAEGO") (field (name "MPN") "RC0402JR-0710KL"))
      (libsource (lib "KON-SU260") (part "RES10K_0402"))
    )
    (comp (ref "R38")
      (value "10K")
      (footprint "KON-SU260:RES0402")
      (description "Resistor, 10k ohm, 0402")
      (fields (field (name "MFG") "YAEGO") (field (name "MPN") "RC0402JR-0710KL"))
      (libsource (lib "KON-SU260") (part "RES10K_0402"))
    )
    (comp (ref "R40")
      (value "10K")
      (footprint "KON-SU260:RES0402")
      (description "Resistor, 10k ohm, 0402")
      (fields (field (name "MFG") "YAEGO") (field (name "MPN") "RC0402JR-0710KL"))
      (libsource (lib "KON-SU260") (part "RES10K_0402"))
    )
    (comp (ref "R45")
      (value "1k")
      (footprint "KON-SU260:RES0402")
      (description "Resistor, 1k, 0402 case, 1%")
      (fields (field (name "MFG") "YAEGO") (field (name "MPN") "RC0402JR-071KL"))
      (libsource (lib "KON-SU260") (part "RES1K_0402"))
    )
    (comp (ref "R47")
      (value "10K")
      (footprint "KON-SU260:RES0402")
      (description "Resistor, 10k ohm, 0402")
      (fields (field (name "MFG") "YAEGO") (field (name "MPN") "RC0402JR-0710KL"))
      (libsource (lib "KON-SU260") (part "RES10K_0402"))
    )
    (comp (ref "R51")
      (value "100K")
      (footprint "KON-SU260:RES0402")
      (description "Resistor, 100k ohm, 0402")
      (fields (field (name "MFG") "PANASONIC") (field (name "MPN") "ERJ-2GEJ104X"))
      (libsource (lib "KON-SU260") (part "RES100K_0402"))
    )
    (comp (ref "R52")
      (value "100K")
      (footprint "KON-SU260:RES0402")
      (description "Resistor, 100k ohm, 0402")
      (fields
        (field (name "MFG") "PANASONIC")
        (field (name "MPN") "ERJ-2GEJ104X")
        (field (name "NP") "Not Populated")
      )
      (libsource (lib "KON-SU260") (part "RES100K_0402"))
    )
    (comp (ref "R65")
      (value "75")
      (footprint "KON-SU260:RES0402")
      (description "Resistor, 75 ohm, 0402, 1%")
      (fields (field (name "MFG") "YAEGO") (field (name "MPN") "RC0402FR-0775RL"))
      (libsource (lib "KON-SU260") (part "RES75R_0402"))
    )
    (comp (ref "R66")
      (value "0")
      (footprint "KON-SU260:RES0402")
      (description "Resistor, 0 ohm, 0402")
      (fields (field (name "MFG") "PANASONIC") (field (name "MPN") "ERJ-2GE0R00X"))
      (libsource (lib "KON-SU260") (part "RES0R_0402"))
    )
    (comp (ref "R2000")
      (value "10K")
      (footprint "KON-SU260:RES0402")
      (description "Resistor, 10k ohm, 0402")
      (fields (field (name "MFG") "YAEGO") (field (name "MPN") "RC0402JR-0710KL"))
      (libsource (lib "KON-SU260") (part "RES10K_0402"))
    )
    (comp (ref "SIM1")
      (value "SIM_CARD_NANO")
      (footprint "SIM_CARD_NANO")
      (description "Connector, SIM Card,Nano")
      (fields
        (field (name "MFG") "GLOBAL CONNECTOR TECHNOLOGY")
        (field (name "MPN") "SIM8050-6-0-14-01-A")
        (field (name "VCC") "VCC")
        (field (name "RST") "RST")
        (field (name "CLK") "CLK")
        (field (name "I/O") "I/O")
        (field (name "VPP") "Vpp")
        (field (name "GND") "GND")
      )
      (libsource (lib "KON-SU260") (part "SIM_CARD_NANO"))
    )
    (comp (ref "SW1")
      (value "SWITCH_PTS810")
      (footprint "SWITCH_PTS810")
      (description "Switch, C&K, PTS810")
      (fields (field (name "MFG") "C&K Components") (field (name "MPN") "PTS810 SJM 250 SMTR LFS"))
      (libsource (lib "KON-SU260") (part "SWITCH_PTS810"))
    )
    (comp (ref "SW2")
      (value "SWITCH_PTS810")
      (footprint "SWITCH_PTS810")
      (description "Switch, C&K, PTS810")
      (fields (field (name "MFG") "C&K Components") (field (name "MPN") "PTS810 SJM 250 SMTR LFS"))
      (libsource (lib "KON-SU260") (part "SWITCH_PTS810"))
    )
    (comp (ref "TP1")
      (value "TPTP08R")
      (footprint "TP08R")
      (description "Test pad")
      (libsource (lib "KON-SU260") (part "TPTP08R"))
    )
    (comp (ref "TP5")
      (value "TPTP08R")
      (footprint "TP08R")
      (description "Test pad")
      (libsource (lib "KON-SU260") (part "TPTP08R"))
    )
    (comp (ref "TP13")
      (value "TPTP08R")
      (footprint "TP08R")
      (description "Test pad")
      (libsource (lib "KON-SU260") (part "TPTP08R"))
    )
    (comp (ref "TP17")
      (value "TPTP08R")
      (footprint "TP08R")
      (description "Test pad")
      (libsource (lib "KON-SU260") (part "TPTP08R"))
    )
    (comp (ref "TP23")
      (value "TPTP08R")
      (footprint "TP08R")
      (description "Test pad")
      (libsource (lib "KON-SU260") (part "TPTP08R"))
    )
    (comp (ref "TP24")
      (value "TPTP08R")
      (footprint "TP08R")
      (description "Test pad")
      (libsource (lib "KON-SU260") (part "TPTP08R"))
    )
    (comp (ref "TP25")
      (value "TPTP08R")
      (footprint "TP08R")
      (description "Test pad")
      (libsource (lib "KON-SU260") (part "TPTP08R"))
    )
    (comp (ref "TP26")
      (value "TPTP08R")
      (footprint "TP08R")
      (description "Test pad")
      (libsource (lib "KON-SU260") (part "TPTP08R"))
    )
    (comp (ref "TP27")
      (value "TPTP08R")
      (footprint "TP08R")
      (description "Test pad")
      (libsource (lib "KON-SU260") (part "TPTP08R"))
    )
    (comp (ref "TP28")
      (value "TPTP08R")
      (footprint "TP08R")
      (description "Test pad")
      (libsource (lib "KON-SU260") (part "TPTP08R"))
    )
    (comp (ref "TP30")
      (value "TPTP08R")
      (footprint "TP08R")
      (description "Test pad")
      (libsource (lib "KON-SU260") (part "TPTP08R"))
    )
    (comp (ref "U$1") (value "TESTPAD") (footprint "TESTPAD") (libsource (lib "KON-SU260") (part "TESTPAD")))
    (comp (ref "U$2") (value "TESTPAD") (footprint "TESTPAD") (libsource (lib "KON-SU260") (part "TESTPAD")))
    (comp (ref "U1")
      (value "MICROCHIP_73871")
      (footprint "QFN50P400X400X80_20_pin")
      (description "Stand-alone Load Sharing and LiPo Battery Charge management controller")
      (fields (field (name "MFG") "MICROCHIP") (field (name "MPN") "MCP73871-2CCI/ML"))
      (libsource (lib "KON-SU260") (part "MICROCHIP_73871"))
    )
    (comp (ref "U2")
      (value "TPS63020")
      (footprint "QFN-14-POWERPAD3X4DSJ")
      (description "Regulator, Boost Buck, Adjustable, 3A")
      (fields (field (name "MFG") "TI") (field (name "MPN") "TPS63020DSJ"))
      (libsource (lib "KON-SU260") (part "TPS63020"))
    )
    (comp (ref "U3")
      (value "CDBQR0230L")
      (footprint "SODFL350X99-2N")
      (description "Schottky Barrier Diode, 1.5 A, 30 V, 0402 package")
      (fields
        (field (name "MFG") "Toshiba Semiconductor and Storage")
        (field (name "MPN") "CRS08(TE85L,Q,M)")
      )
      (libsource (lib "KON-SU260") (part "DIODE_SOD123F_1A"))
    )
    (comp (ref "U4")
      (value "CDBQR0230L")
      (footprint "SODFL350X99-2N")
      (description "Schottky Barrier Diode, 1.5 A, 30 V, 0402 package")
      (fields
        (field (name "MFG") "Toshiba Semiconductor and Storage")
        (field (name "MPN") "CRS08(TE85L,Q,M)")
      )
      (libsource (lib "KON-SU260") (part "DIODE_SOD123F_1A"))
    )
    (comp (ref "U5")
      (value "MK22FN1M0VLH12")
      (footprint "KON-SU260:LQFP-64N")
      (description "ARM® Cortex®-M4 Kinetis K20 Microcontroller IC 32-Bit 120MHz 1MB (1M x 8) FLASH 64-LQFP (10x10)")
      (fields (field (name "MPN") "MK22FN1M0AVLH12") (field (name "MFG") "Freescale"))
      (libsource (lib "KON-SU260") (part "MK22FN1M0VLH12"))
    )
    (comp (ref "U6")
      (value "FREESCALE_MKL17Z256VFM4")
      (footprint "KON-SU260:QFN50P50")
      (description "Microprocessor, Freescale, MKL17Z256VFM4")
      (fields
        (field (name "MFG") "FREESCALE")
        (field (name "MPN") "MKL17Z256VFM4")
        (field (name "SPI0_SS") "SPI0_SS")
        (field (name "UART2_TX") "UART2_TX")
        (field (name "SPI0_SCK") "SPI0_SCK")
        (field (name "UART2_RX") "UART2_RX")
        (field (name "SPI0_MOSI") "SPI0_MOSI")
        (field (name "SPI0_MISO") "SPI0_MISO")
        (field (name "SWD_CLK") "SWD_CLK")
        (field (name "SWD_DIO") "SWD_DIO")
        (field (name "EXTAL0") "EXTAL0")
        (field (name "XTAL0") "XTAL0")
        (field (name "LPUART0_RX") "LPUART0_RX")
        (field (name "LPUART0_TX") "LPUART0_TX")
        (field (name "I2C0_SCL") "I2C0_SCL")
        (field (name "I2C0_SDA") "I2C0_SDA")
        (field (name "LPUART1_TX") "LPUART1_TX")
        (field (name "SPI1_SS") "SPI1_SS")
        (field (name "SPI1_SCK") "SPI1_SCK")
        (field (name "SPI1_MOSI") "SPI1_MOSI")
        (field (name "MKL17Z256VFM4") "MKL17Z256VFM4")
        (field (name "SPI1_MISO") "SPI1_MISO")
        (field (name "I2C1_SCL") "I2C1_SCL")
        (field (name "I2C1_SDA") "I2C1_SDA")
        (field (name "LPUART1_RX") "LPUART1_RX")
      )
      (libsource (lib "KON-SU260") (part "FREESCALE_MKL17Z256VFM4"))
    )
    (comp (ref "U8")
      (value "VOLTAGE_TRANSLATOR_4_BIT")
      (footprint "UQFN_16")
      (description "IC, Voltage Translator, 4-bit")
      (fields (field (name "MFG") "TI") (field (name "MPN") "SN74AVC4T774RSVR"))
      (libsource (lib "KON-SU260") (part "VOLTAGE_TRANSLATOR_4_BIT"))
    )
    (comp (ref "U9")
      (value "~")
      (footprint "KON-SU260:SC70-5")
      (description "IC, Current-limited  Load Switch, Active High")
      (fields (field (name "MFG") "Texas Instruments") (field (name "MPN") "TPS22945DCKR"))
      (libsource (lib "KON-SU260") (part "TPS22945"))
    )
    (comp (ref "U10")
      (value "~")
      (footprint "KON-SU260:XDFN-4")
      (description "IC Regulator, LDO 3.3V 0.5A, 4XDFN")
      (fields (field (name "MFG") "On Semi") (field (name "MPN") "NCP177AMX330TCG"))
      (libsource (lib "KON-SU260") (part "NCP177-D"))
    )
    (comp (ref "U16")
      (value "SARA-U2XX")
      (footprint "KON-SU260:SARA")
      (description "Module, uBlox, SARA-U2xx")
      (fields (field (name "MFG") "U-BLOX") (field (name "MPN") "SARA-U260-00S"))
      (libsource (lib "KON-SU260") (part "SARA-U2XX"))
    )
    (comp (ref "U19")
      (value "MAX1704X")
      (footprint "TDFN-8")
      (description "MAX17043/MAX17044: Battery Fuel Guage (43 is 1cell, 44 is 2cell)")
      (fields (field (name "MFG") "Maxim") (field (name "MPN") "MAX17043G+U"))
      (libsource (lib "KON-SU260") (part "MAX1704X"))
    )
    (comp (ref "X1")
      (value "CRYSTAL_16MHz")
      (footprint "CRYSTAL-SMD-2X1.6")
      (description "Crystal SMD, 16 MHz")
      (fields (field (name "MPN") "CX2016DB16000D0WZRC1") (field (name "MFG") "AVX"))
      (libsource (lib "KON-SU260") (part "CRYSTAL_16MHz"))
    )
    (comp (ref "X2")
      (value "32.768 kHz")
      (footprint "CRYSTAL_ABS05")
      (description "32.768kHz ±20ppm Crystal 12.5pF 90 kOhm -40°C ~ 85°C Surface Mount 2-SMD")
      (fields (field (name "MFG") "Abracon") (field (name "MPN") "ABS05-32.768KHZ-T"))
      (libsource (lib "KON-SU260") (part "CRYSTAL_32.768K_ABS05"))
    )
    (comp (ref "X3")
      (value "32.768 kHz")
      (footprint "CRYSTAL_ABS05")
      (description "32.768kHz ±20ppm Crystal 12.5pF 90 kOhm -40°C ~ 85°C Surface Mount 2-SMD")
      (fields (field (name "MFG") "Abracon") (field (name "MPN") "ABS05-32.768KHZ-T"))
      (libsource (lib "KON-SU260") (part "CRYSTAL_32.768K_ABS05"))
    )
  )
  (nets
    (net (code "1") (name "/+3.3V") (class "Default")
      (node (ref "C27") (pin "1") (pinfunction "1_1") (pintype "passive"))
      (node (ref "C28") (pin "1") (pinfunction "1_1") (pintype "passive"))
      (node (ref "C3") (pin "1") (pinfunction "1_1") (pintype "passive"))
      (node (ref "C4") (pin "1") (pinfunction "1_1") (pintype "passive"))
      (node (ref "C49") (pin "1") (pinfunction "1_1") (pintype "passive"))
      (node (ref "C7") (pin "1") (pinfunction "1_1") (pintype "passive"))
      (node (ref "C8") (pin "1") (pinfunction "1_1") (pintype "passive"))
      (node (ref "C9") (pin "1") (pinfunction "1_1") (pintype "passive"))
      (node (ref "D2") (pin "1") (pinfunction "Common_ANODE_1") (pintype "passive"))
      (node (ref "JRIGHT") (pin "12") (pinfunction "12_12") (pintype "passive"))
      (node (ref "L1") (pin "1") (pinfunction "P$1_1") (pintype "passive"))
      (node (ref "R24") (pin "2") (pinfunction "2_2") (pintype "passive"))
      (node (ref "R35") (pin "2") (pinfunction "2_2") (pintype "passive"))
      (node (ref "R36") (pin "2") (pinfunction "2_2") (pintype "passive"))
      (node (ref "R37") (pin "2") (pinfunction "2_2") (pintype "passive"))
      (node (ref "R38") (pin "2") (pinfunction "2_2") (pintype "passive"))
      (node (ref "R40") (pin "2") (pinfunction "2_2") (pintype "passive"))
      (node (ref "R47") (pin "2") (pinfunction "2_2") (pintype "passive"))
      (node (ref "U10") (pin "1") (pinfunction "OUT_1") (pintype "passive"))
      (node (ref "U19") (pin "3") (pinfunction "VDD_3") (pintype "passive"))
      (node (ref "U5") (pin "21") (pinfunction "VBAT_21") (pintype "passive"))
      (node (ref "U5") (pin "3") (pinfunction "VDD_3") (pintype "passive"))
      (node (ref "U5") (pin "30") (pinfunction "VDD1_30") (pintype "passive"))
      (node (ref "U5") (pin "48") (pinfunction "VDD2_48") (pintype "passive"))
      (node (ref "U6") (pin "15") (pinfunction "VDD_15") (pintype "passive"))
      (node (ref "U6") (pin "7") (pinfunction "VDDA_7") (pintype "passive"))
      (node (ref "U9") (pin "5") (pinfunction "VIN_5") (pintype "passive"))
    )
    (net (code "2") (name "/+3.8V") (class "Default")
      (node (ref "C16") (pin "1") (pinfunction "1_1") (pintype "passive"))
      (node (ref "C36") (pin "1") (pinfunction "1_1") (pintype "passive"))
      (node (ref "C37") (pin "1") (pinfunction "1_1") (pintype "passive"))
      (node (ref "C38") (pin "1") (pinfunction "1_1") (pintype "passive"))
      (node (ref "L7") (pin "2") (pinfunction "P$2_2") (pintype "passive"))
      (node (ref "R13") (pin "2") (pinfunction "2_2") (pintype "passive"))
      (node (ref "TP30") (pin "TP") (pinfunction "TP_TP") (pintype "passive"))
      (node (ref "U10") (pin "3") (pinfunction "EN_3") (pintype "passive"))
      (node (ref "U10") (pin "4") (pinfunction "VIN_4") (pintype "passive"))
      (node (ref "U2") (pin "4") (pinfunction "VOUT_4") (pintype "passive"))
      (node (ref "U2") (pin "5") (pinfunction "VOUT_5") (pintype "passive"))
    )
    (net (code "3") (name "/AGND") (class "Default")
      (node (ref "C13") (pin "2") (pinfunction "2_2") (pintype "passive"))
      (node (ref "C14") (pin "2") (pinfunction "2_2") (pintype "passive"))
      (node (ref "C15") (pin "2") (pinfunction "2_2") (pintype "passive"))
      (node (ref "L3") (pin "1") (pinfunction "P$1_1") (pintype "passive"))
      (node (ref "U5") (pin "15") (pinfunction "VREFL_15") (pintype "passive"))
      (node (ref "U5") (pin "16") (pinfunction "VSSA_16") (pintype "passive"))
    )
    (net (code "4") (name "/AREF") (class "Default")
      (node (ref "C14") (pin "1") (pinfunction "1_1") (pintype "passive"))
      (node (ref "R19") (pin "2") (pinfunction "2_2") (pintype "passive"))
      (node (ref "U5") (pin "14") (pinfunction "VREFH_14") (pintype "passive"))
    )
    (net (code "5") (name "/BL_SCL") (class "Default")
      (node (ref "R40") (pin "1") (pinfunction "1_1") (pintype "passive"))
      (node (ref "U19") (pin "7") (pinfunction "SCL_7") (pintype "passive"))
      (node (ref "U5") (pin "37") (pinfunction "PTB2_37") (pintype "passive"))
      (node (ref "U6") (pin "20") (pinfunction "PTB0_20") (pintype "passive"))
    )
    (net (code "6") (name "/BL_SDA") (class "Default")
      (node (ref "R35") (pin "1") (pinfunction "1_1") (pintype "passive"))
      (node (ref "U19") (pin "8") (pinfunction "SDA_8") (pintype "passive"))
      (node (ref "U5") (pin "38") (pinfunction "PTB3_38") (pintype "passive"))
      (node (ref "U6") (pin "21") (pinfunction "PTB1_21") (pintype "passive"))
    )
    (net (code "7") (name "/CHG_PG") (class "Default")
      (node (ref "R38") (pin "1") (pinfunction "1_1") (pintype "passive"))
      (node (ref "U1") (pin "6") (pinfunction "~{PG}_6") (pintype "passive"))
      (node (ref "U6") (pin "9") (pinfunction "DAC0_OUT_PTE_30_9") (pintype "passive"))
    )
    (net (code "8") (name "/CHG_ST1") (class "Default")
      (node (ref "R37") (pin "1") (pinfunction "1_1") (pintype "passive"))
      (node (ref "U1") (pin "8") (pinfunction "STAT1/~{LBO}_8") (pintype "passive"))
      (node (ref "U6") (pin "12") (pinfunction "PTA2_12") (pintype "passive"))
    )
    (net (code "9") (name "/CHG_ST2") (class "Default")
      (node (ref "R36") (pin "1") (pinfunction "1_1") (pintype "passive"))
      (node (ref "U1") (pin "7") (pinfunction "STAT2_7") (pintype "passive"))
      (node (ref "U6") (pin "2") (pinfunction "PTE1_2") (pintype "passive"))
    )
    (net (code "10") (name "/EZP_CS") (class "Default")
      (node (ref "U5") (pin "26") (pinfunction "PTA4_26") (pintype "passive"))
      (node (ref "U6") (pin "3") (pinfunction "PTE16_3") (pintype "passive"))
    )
    (net (code "11") (name "/PWM_B") (class "Default")
      (node (ref "R21") (pin "1") (pinfunction "1_1") (pintype "passive"))
      (node (ref "U6") (pin "30") (pinfunction "PTD5_30") (pintype "passive"))
    )
    (net (code "12") (name "/PWM_G") (class "Default")
      (node (ref "R22") (pin "1") (pinfunction "1_1") (pintype "passive"))
      (node (ref "U6") (pin "29") (pinfunction "PTD4_29") (pintype "passive"))
    )
    (net (code "13") (name "/PWM_R") (class "Default")
      (node (ref "R20") (pin "1") (pinfunction "1_1") (pintype "passive"))
      (node (ref "U6") (pin "23") (pinfunction "PTC2_23") (pintype "passive"))
    )
    (net (code "14") (name "/SYS_RESET") (class "Default")
      (node (ref "JRIGHT") (pin "10") (pinfunction "10_10") (pintype "passive"))
      (node (ref "U5") (pin "41") (pinfunction "PTB18_41") (pintype "passive"))
      (node (ref "U6") (pin "19") (pinfunction "RESET_B_PTA20_19") (pintype "passive"))
    )
    (net (code "15") (name "/SYS_TCK_SWDCLK") (class "Default")
      (node (ref "JRIGHT") (pin "18") (pinfunction "18_18") (pintype "passive"))
      (node (ref "TP17") (pin "TP") (pinfunction "TP_TP") (pintype "passive"))
      (node (ref "U6") (pin "10") (pinfunction "PTA0_10") (pintype "passive"))
    )
    (net (code "16") (name "/SYS_TMS_SWDIO") (class "Default")
      (node (ref "JLEFT") (pin "18") (pinfunction "18_18") (pintype "passive"))
      (node (ref "TP27") (pin "TP") (pinfunction "TP_TP") (pintype "passive"))
      (node (ref "U6") (pin "13") (pinfunction "PTA3_13") (pintype "passive"))
    )
    (net (code "17") (name "/SYS_TX_TO_USR_RX") (class "Default")
      (node (ref "TP25") (pin "TP") (pinfunction "TP_TP") (pintype "passive"))
      (node (ref "U5") (pin "46") (pinfunction "PTC3_46") (pintype "passive"))
      (node (ref "U6") (pin "25") (pinfunction "PTC4_25") (pintype "passive"))
    )
    (net (code "18") (name "/SYS_UBLOX_RX") (class "Default")
      (node (ref "U6") (pin "31") (pinfunction "PTD6_31") (pintype "passive"))
      (node (ref "U8") (pin "P$4") (pinfunction "A4_P$4") (pintype "passive"))
    )
    (net (code "19") (name "/SYS_UBLOX_TX") (class "Default")
      (node (ref "U6") (pin "32") (pinfunction "PTD7_32") (pintype "passive"))
      (node (ref "U8") (pin "P$3") (pinfunction "A3_P$3") (pintype "passive"))
    )
    (net (code "20") (name "/SystemVin") (class "Default")
      (node (ref "C1") (pin "1") (pinfunction "1_1") (pintype "passive"))
      (node (ref "JLEFT") (pin "1") (pinfunction "1_1") (pintype "passive"))
      (node (ref "U1") (pin "17") (pinfunction "CE_17") (pintype "passive"))
      (node (ref "U1") (pin "18") (pinfunction "Vin_18") (pintype "passive"))
      (node (ref "U1") (pin "19") (pinfunction "Vin_19") (pintype "passive"))
      (node (ref "U1") (pin "2") (pinfunction "VPCC_2") (pintype "passive"))
      (node (ref "U1") (pin "3") (pinfunction "SEL_3") (pintype "passive"))
      (node (ref "U1") (pin "4") (pinfunction "PROG2_4") (pintype "passive"))
      (node (ref "U1") (pin "9") (pinfunction "~{TE}_9") (pintype "passive"))
      (node (ref "U3") (pin "CATHODE") (pinfunction "CATHODE_CATHODE") (pintype "passive"))
    )
    (net (code "21") (name "/TXL_ON_N") (class "Default")
      (node (ref "U6") (pin "1") (pinfunction "PTE0_1") (pintype "passive"))
      (node (ref "U9") (pin "4") (pinfunction "ON_4") (pintype "passive"))
    )
    (net (code "22") (name "/TXL_VCC") (class "Default")
      (node (ref "C26") (pin "1") (pinfunction "1_1") (pintype "passive"))
      (node (ref "U8") (pin "P$14") (pinfunction "VCCA_P$14") (pintype "power_in"))
      (node (ref "U8") (pin "P$15") (pinfunction "DIR1_P$15") (pintype "passive"))
      (node (ref "U8") (pin "P$5") (pinfunction "DIR3_P$5") (pintype "passive"))
      (node (ref "U9") (pin "1") (pinfunction "VOUT_1") (pintype "passive"))
    )
    (net (code "23") (name "/UBLOX_1.8V_SUPPLY") (class "Default")
      (node (ref "C25") (pin "1") (pinfunction "1_1") (pintype "passive"))
      (node (ref "U16") (pin "4") (pinfunction "V_INT$4_4") (pintype "passive"))
      (node (ref "U8") (pin "P$13") (pinfunction "VCCB_P$13") (pintype "power_in"))
    )
    (net (code "24") (name "/UBLOX_ANT") (class "Default")
      (node (ref "ANT_UFL") (pin "SIGNAL") (pinfunction "SIGNAL_SIGNAL") (pintype "passive"))
      (node (ref "U16") (pin "56") (pinfunction "ANT$56_56") (pintype "power_in"))
    )
    (net (code "25") (name "/UBLOX_ANT_IND") (class "Default")
      (node (ref "U16") (pin "16") (pinfunction "GPIO1$16_16") (pintype "passive"))
    )
    (net (code "26") (name "/UBLOX_PWR_ON") (class "Default")
      (node (ref "R51") (pin "1") (pinfunction "1_1") (pintype "passive"))
      (node (ref "R52") (pin "2") (pinfunction "2_2") (pintype "passive"))
      (node (ref "U16") (pin "15") (pinfunction "PWR_ON$15_15") (pintype "passive"))
      (node (ref "U6") (pin "14") (pinfunction "PTA4_14") (pintype "passive"))
    )
    (net (code "27") (name "/UBLOX_RESET_N") (class "Default")
      (node (ref "C43") (pin "1") (pinfunction "1_1") (pintype "passive"))
      (node (ref "R11") (pin "1") (pinfunction "1_1") (pintype "passive"))
      (node (ref "U16") (pin "18") (pinfunction "RESET_N$18_18") (pintype "passive"))
      (node (ref "U6") (pin "11") (pinfunction "PTA1_11") (pintype "passive"))
    )
    (net (code "28") (name "/UBLOX_RXD") (class "Default")
      (node (ref "TP24") (pin "TP") (pinfunction "TP_TP") (pintype "passive"))
      (node (ref "U16") (pin "13") (pinfunction "RXD$13_13") (pintype "passive"))
      (node (ref "U8") (pin "P$9") (pinfunction "B4_P$9") (pintype "passive"))
    )
    (net (code "29") (name "/UBLOX_SARA_USB_D_N") (class "Default")
      (node (ref "U$2") (pin "P$1") (pinfunction "P$1_P$1") (pintype "passive"))
      (node (ref "U16") (pin "28") (pinfunction "USB_D-$28_28") (pintype "power_in"))
    )
    (net (code "30") (name "/UBLOX_SARA_USB_D_P") (class "Default")
      (node (ref "U$1") (pin "P$1") (pinfunction "P$1_P$1") (pintype "passive"))
      (node (ref "U16") (pin "29") (pinfunction "USB_D+$29_29") (pintype "power_in"))
    )
    (net (code "31") (name "/UBLOX_SIM_CLK") (class "Default")
      (node (ref "C42") (pin "1") (pinfunction "1_1") (pintype "passive"))
      (node (ref "D9") (pin "2") (pinfunction "2_2") (pintype "passive"))
      (node (ref "SIM1") (pin "C3") (pinfunction "CLK_C3") (pintype "passive"))
      (node (ref "U16") (pin "38") (pinfunction "SIM_CLK$38_38") (pintype "power_in"))
    )
    (net (code "32") (name "/UBLOX_SIM_IO") (class "Default")
      (node (ref "C44") (pin "1") (pinfunction "1_1") (pintype "passive"))
      (node (ref "D10") (pin "2") (pinfunction "2_2") (pintype "passive"))
      (node (ref "SIM1") (pin "C7") (pinfunction "IO_C7") (pintype "passive"))
      (node (ref "U16") (pin "39") (pinfunction "SIM_IO$39_39") (pintype "power_in"))
    )
    (net (code "33") (name "/UBLOX_SIM_RST") (class "Default")
      (node (ref "C41") (pin "1") (pinfunction "1_1") (pintype "passive"))
      (node (ref "D6") (pin "2") (pinfunction "2_2") (pintype "passive"))
      (node (ref "SIM1") (pin "C2") (pinfunction "RST_C2") (pintype "passive"))
      (node (ref "U16") (pin "40") (pinfunction "SIM_RST$40_40") (pintype "power_in"))
    )
    (net (code "34") (name "/UBLOX_SIM_VSIM") (class "Default")
      (node (ref "C2") (pin "1") (pinfunction "1_1") (pintype "passive"))
      (node (ref "C45") (pin "1") (pinfunction "1_1") (pintype "passive"))
      (node (ref "D11") (pin "2") (pinfunction "2_2") (pintype "passive"))
      (node (ref "SIM1") (pin "C1") (pinfunction "VCC_C1") (pintype "passive"))
      (node (ref "SIM1") (pin "C6") (pinfunction "VCC2_C6") (pintype "passive"))
      (node (ref "U16") (pin "41") (pinfunction "VSIM$41_41") (pintype "passive"))
    )
    (net (code "35") (name "/UBLOX_TXD") (class "Default")
      (node (ref "TP23") (pin "TP") (pinfunction "TP_TP") (pintype "passive"))
      (node (ref "U16") (pin "12") (pinfunction "TXD$12_12") (pintype "power_in"))
      (node (ref "U8") (pin "P$10") (pinfunction "B3_P$10") (pintype "passive"))
    )
    (net (code "36") (name "/UBLOX_VCC") (class "Default")
      (node (ref "C39") (pin "1") (pinfunction "1_1") (pintype "passive"))
      (node (ref "C40") (pin "1") (pinfunction "1_1") (pintype "passive"))
      (node (ref "C46") (pin "1") (pinfunction "1_1") (pintype "passive"))
      (node (ref "C47") (pin "1") (pinfunction "1_1") (pintype "passive"))
      (node (ref "C6") (pin "1") (pinfunction "1_1") (pintype "passive"))
      (node (ref "L7") (pin "1") (pinfunction "P$1_1") (pintype "passive"))
      (node (ref "TP28") (pin "TP") (pinfunction "TP_TP") (pintype "passive"))
      (node (ref "U16") (pin "51") (pinfunction "VCC$51_51") (pintype "passive"))
      (node (ref "U16") (pin "52") (pinfunction "VCC$52_52") (pintype "passive"))
      (node (ref "U16") (pin "53") (pinfunction "VCC$53_53") (pintype "passive"))
    )
    (net (code "37") (name "/UBLOX_V_BCKP") (class "Default")
      (node (ref "R11") (pin "2") (pinfunction "2_2") (pintype "passive"))
      (node (ref "R51") (pin "2") (pinfunction "2_2") (pintype "passive"))
      (node (ref "U16") (pin "2") (pinfunction "V_BCKP$2_2") (pintype "passive"))
    )
    (net (code "38") (name "/USB_5V") (class "Default")
      (node (ref "F6") (pin "1") (pinfunction "P$1_1") (pintype "passive"))
      (node (ref "J1") (pin "VCC") (pinfunction "VBUS_VCC") (pintype "passive"))
      (node (ref "TP1") (pin "TP") (pinfunction "TP_TP") (pintype "passive"))
    )
    (net (code "39") (name "/USB_D_N") (class "Default")
      (node (ref "D4") (pin "2") (pinfunction "2_2") (pintype "passive"))
      (node (ref "R1") (pin "2") (pinfunction "2_2") (pintype "passive"))
      (node (ref "U5") (pin "6") (pinfunction "USB0_DM_6") (pintype "passive"))
    )
    (net (code "40") (name "/USB_D_P") (class "Default")
      (node (ref "D3") (pin "2") (pinfunction "2_2") (pintype "passive"))
      (node (ref "R2") (pin "2") (pinfunction "2_2") (pintype "passive"))
      (node (ref "U5") (pin "5") (pinfunction "USB0_DP_5") (pintype "passive"))
    )
    (net (code "41") (name "/USB_ID") (class "Default")
      (node (ref "J1") (pin "ID") (pinfunction "ID_ID") (pintype "passive"))
      (node (ref "R66") (pin "1") (pinfunction "1_1") (pintype "passive"))
    )
    (net (code "42") (name "/USB_IN") (class "Default")
      (node (ref "C11") (pin "1") (pinfunction "1_1") (pintype "passive"))
      (node (ref "C12") (pin "1") (pinfunction "1_1") (pintype "passive"))
      (node (ref "D5") (pin "2") (pinfunction "2_2") (pintype "passive"))
      (node (ref "F6") (pin "2") (pinfunction "P$2_2") (pintype "passive"))
      (node (ref "L2") (pin "2") (pinfunction "P$2_2") (pintype "passive"))
      (node (ref "TP5") (pin "TP") (pinfunction "TP_TP") (pintype "passive"))
      (node (ref "U3") (pin "ANODE") (pinfunction "ANODE_ANODE") (pintype "passive"))
    )
    (net (code "43") (name "/USB_IN_D_N") (class "Default")
      (node (ref "J1") (pin "D-") (pinfunction "D-_D-") (pintype "passive"))
      (node (ref "R1") (pin "1") (pinfunction "1_1") (pintype "passive"))
    )
    (net (code "44") (name "/USB_IN_D_P") (class "Default")
      (node (ref "J1") (pin "D+") (pinfunction "D+_D+") (pintype "passive"))
      (node (ref "R2") (pin "1") (pinfunction "1_1") (pintype "passive"))
    )
    (net (code "45") (name "/USER01") (class "Default")
      (node (ref "JLEFT") (pin "12") (pinfunction "12_12") (pintype "passive"))
      (node (ref "U5") (pin "29") (pinfunction "PTA13_29") (pintype "passive"))
    )
    (net (code "46") (name "/USER02") (class "Default")
      (node (ref "JLEFT") (pin "11") (pinfunction "11_11") (pintype "passive"))
      (node (ref "U5") (pin "28") (pinfunction "PTA12_28") (pintype "passive"))
    )
    (net (code "47") (name "/USER03") (class "Default")
      (node (ref "JLEFT") (pin "10") (pinfunction "10_10") (pintype "passive"))
      (node (ref "U5") (pin "27") (pinfunction "PTA5_27") (pintype "passive"))
    )
    (net (code "48") (name "/USER04") (class "Default")
      (node (ref "JLEFT") (pin "3") (pinfunction "3_3") (pintype "passive"))
      (node (ref "U5") (pin "1") (pinfunction "PTE0_1") (pintype "passive"))
    )
    (net (code "49") (name "/USER05") (class "Default")
      (node (ref "JLEFT") (pin "4") (pinfunction "4_4") (pintype "passive"))
      (node (ref "U5") (pin "2") (pinfunction "PTE1_2") (pintype "passive"))
    )
    (net (code "50") (name "/USER06") (class "Default")
      (node (ref "JLEFT") (pin "13") (pinfunction "13_13") (pintype "passive"))
      (node (ref "U5") (pin "35") (pinfunction "PTB0_35") (pintype "passive"))
    )
    (net (code "51") (name "/USER07") (class "Default")
      (node (ref "JLEFT") (pin "9") (pinfunction "9_9") (pintype "passive"))
      (node (ref "U5") (pin "36") (pinfunction "PTB1_36") (pintype "passive"))
    )
    (net (code "52") (name "/USER08") (class "Default")
      (node (ref "JLEFT") (pin "14") (pinfunction "14_14") (pintype "passive"))
      (node (ref "U5") (pin "18") (pinfunction "DAC0_OUT_18") (pintype "passive"))
    )
    (net (code "53") (name "/USER09") (class "Default")
      (node (ref "JRIGHT") (pin "8") (pinfunction "8_8") (pintype "passive"))
      (node (ref "U5") (pin "45") (pinfunction "PTC2_45") (pintype "passive"))
    )
    (net (code "54") (name "/USER10") (class "Default")
      (node (ref "JRIGHT") (pin "7") (pinfunction "7_7") (pintype "passive"))
      (node (ref "U5") (pin "44") (pinfunction "PTC1_44") (pintype "passive"))
    )
    (net (code "55") (name "/USER11") (class "Default")
      (node (ref "JRIGHT") (pin "9") (pinfunction "9_9") (pintype "passive"))
      (node (ref "U5") (pin "43") (pinfunction "PTC0_43") (pintype "passive"))
    )
    (net (code "56") (name "/USER12") (class "Default")
      (node (ref "JRIGHT") (pin "6") (pinfunction "6_6") (pintype "passive"))
      (node (ref "U5") (pin "53") (pinfunction "PTC8_53") (pintype "passive"))
    )
    (net (code "57") (name "/USER13") (class "Default")
      (node (ref "JLEFT") (pin "5") (pinfunction "5_5") (pintype "passive"))
      (node (ref "U5") (pin "58") (pinfunction "PTD1_58") (pintype "passive"))
    )
    (net (code "58") (name "/USER14") (class "Default")
      (node (ref "JLEFT") (pin "6") (pinfunction "6_6") (pintype "passive"))
      (node (ref "U5") (pin "59") (pinfunction "PTD2_59") (pintype "passive"))
    )
    (net (code "59") (name "/USER15") (class "Default")
      (node (ref "JLEFT") (pin "8") (pinfunction "8_8") (pintype "passive"))
      (node (ref "U5") (pin "60") (pinfunction "PTD3_60") (pintype "passive"))
    )
    (net (code "60") (name "/USER16") (class "Default")
      (node (ref "JRIGHT") (pin "4") (pinfunction "4_4") (pintype "passive"))
      (node (ref "U5") (pin "61") (pinfunction "PTD4_61") (pintype "passive"))
    )
    (net (code "61") (name "/USER17") (class "Default")
      (node (ref "JLEFT") (pin "7") (pinfunction "7_7") (pintype "passive"))
      (node (ref "U5") (pin "62") (pinfunction "PTD5_62") (pintype "passive"))
    )
    (net (code "62") (name "/USER18") (class "Default")
      (node (ref "JRIGHT") (pin "5") (pinfunction "5_5") (pintype "passive"))
      (node (ref "U5") (pin "63") (pinfunction "PTD6_63") (pintype "passive"))
    )
    (net (code "63") (name "/USER19") (class "Default")
      (node (ref "JRIGHT") (pin "3") (pinfunction "3_3") (pintype "passive"))
      (node (ref "U5") (pin "64") (pinfunction "PTD7_64") (pintype "passive"))
    )
    (net (code "64") (name "/USER23") (class "Default")
      (node (ref "JRIGHT") (pin "13") (pinfunction "13_13") (pintype "passive"))
      (node (ref "U5") (pin "51") (pinfunction "PTC6_51") (pintype "passive"))
    )
    (net (code "65") (name "/USER24") (class "Default")
      (node (ref "JRIGHT") (pin "14") (pinfunction "14_14") (pintype "passive"))
      (node (ref "U5") (pin "52") (pinfunction "PTC7_52") (pintype "passive"))
    )
    (net (code "66") (name "/USER26") (class "Default")
      (node (ref "JRIGHT") (pin "15") (pinfunction "15_15") (pintype "passive"))
      (node (ref "U5") (pin "55") (pinfunction "PTC10_55") (pintype "passive"))
    )
    (net (code "67") (name "/USER27") (class "Default")
      (node (ref "JRIGHT") (pin "17") (pinfunction "17_17") (pintype "passive"))
      (node (ref "U5") (pin "56") (pinfunction "PTC11_56") (pintype "passive"))
    )
    (net (code "68") (name "/USER28") (class "Default")
      (node (ref "JRIGHT") (pin "16") (pinfunction "16_16") (pintype "passive"))
      (node (ref "U5") (pin "57") (pinfunction "PTD0_57") (pintype "passive"))
    )
    (net (code "69") (name "/USER_PROGRAM") (class "Default")
      (node (ref "JRIGHT") (pin "11") (pinfunction "11_11") (pintype "passive"))
      (node (ref "R24") (pin "1") (pinfunction "1_1") (pintype "passive"))
      (node (ref "SW2") (pin "1") (pinfunction "P$1_1") (pintype "passive"))
      (node (ref "SW2") (pin "2") (pinfunction "P$1_2") (pintype "passive"))
      (node (ref "U5") (pin "54") (pinfunction "PTC9_54") (pintype "passive"))
      (node (ref "U6") (pin "27") (pinfunction "PTC6_27") (pintype "passive"))
    )
    (net (code "70") (name "/USR_LED") (class "Default")
      (node (ref "D1") (pin "ANODE") (pinfunction "ANODE_ANODE") (pintype "passive"))
      (node (ref "U5") (pin "42") (pinfunction "PTB19_42") (pintype "passive"))
    )
    (net (code "71") (name "/USR_RESET") (class "Default")
      (node (ref "C24") (pin "1") (pinfunction "1_1") (pintype "passive"))
      (node (ref "JLEFT") (pin "15") (pinfunction "15_15") (pintype "passive"))
      (node (ref "R47") (pin "1") (pinfunction "1_1") (pintype "passive"))
      (node (ref "SW1") (pin "1") (pinfunction "P$1_1") (pintype "passive"))
      (node (ref "SW1") (pin "2") (pinfunction "P$1_2") (pintype "passive"))
      (node (ref "U5") (pin "34") (pinfunction "RESET_B_34") (pintype "passive"))
      (node (ref "U6") (pin "26") (pinfunction "PTC5_26") (pintype "passive"))
    )
    (net (code "72") (name "/USR_TCK_SWDCLK") (class "Default")
      (node (ref "JLEFT") (pin "17") (pinfunction "17_17") (pintype "passive"))
      (node (ref "U5") (pin "22") (pinfunction "PTA0_22") (pintype "passive"))
      (node (ref "U6") (pin "4") (pinfunction "PTE17_4") (pintype "passive"))
    )
    (net (code "73") (name "/USR_TDI") (class "Default")
      (node (ref "R66") (pin "2") (pinfunction "2_2") (pintype "passive"))
      (node (ref "U5") (pin "23") (pinfunction "PTA1_23") (pintype "passive"))
      (node (ref "U6") (pin "5") (pinfunction "PTE18_5") (pintype "passive"))
    )
    (net (code "74") (name "/USR_TDO_SWO") (class "Default")
      (node (ref "U5") (pin "24") (pinfunction "PTA2_24") (pintype "passive"))
      (node (ref "U6") (pin "6") (pinfunction "PTE19_6") (pintype "passive"))
    )
    (net (code "75") (name "/USR_TMS_SWDIO") (class "Default")
      (node (ref "JLEFT") (pin "16") (pinfunction "16_16") (pintype "passive"))
      (node (ref "U5") (pin "25") (pinfunction "PTA3_25") (pintype "passive"))
      (node (ref "U6") (pin "22") (pinfunction "PTC1_22") (pintype "passive"))
    )
    (net (code "76") (name "/USR_TX_TO_SYS_RX") (class "Default")
      (node (ref "TP26") (pin "TP") (pinfunction "TP_TP") (pintype "passive"))
      (node (ref "U5") (pin "49") (pinfunction "PTC4_49") (pintype "passive"))
      (node (ref "U6") (pin "24") (pinfunction "PTC3_24") (pintype "passive"))
    )
    (net (code "77") (name "/VBATT") (class "Default")
      (node (ref "J20") (pin "BAT") (pinfunction "BAT_BAT") (pintype "passive"))
      (node (ref "R45") (pin "2") (pinfunction "2_2") (pintype "passive"))
      (node (ref "TP13") (pin "TP") (pinfunction "TP_TP") (pintype "passive"))
      (node (ref "U1") (pin "14") (pinfunction "Vbat_14") (pintype "passive"))
      (node (ref "U1") (pin "15") (pinfunction "Vbat_15") (pintype "passive"))
      (node (ref "U1") (pin "16") (pinfunction "Vbat_16") (pintype "passive"))
    )
    (net (code "78") (name "/VOUT33") (class "Default")
      (node (ref "C10") (pin "1") (pinfunction "1_1") (pintype "passive"))
      (node (ref "U5") (pin "7") (pinfunction "VOUT33_7") (pintype "passive"))
    )
    (net (code "79") (name "/VREGIN") (class "Default")
      (node (ref "C18") (pin "1") (pinfunction "1_1") (pintype "passive"))
      (node (ref "U4") (pin "CATHODE") (pinfunction "CATHODE_CATHODE") (pintype "passive"))
      (node (ref "U5") (pin "8") (pinfunction "VREGIN_8") (pintype "passive"))
    )
    (net (code "80") (name "/VSystem") (class "Default")
      (node (ref "C33") (pin "1") (pinfunction "1_1") (pintype "passive"))
      (node (ref "C34") (pin "1") (pinfunction "1_1") (pintype "passive"))
      (node (ref "D8") (pin "ANODE") (pinfunction "ANODE_ANODE") (pintype "passive"))
      (node (ref "U1") (pin "1") (pinfunction "OUT_1") (pintype "passive"))
      (node (ref "U1") (pin "20") (pinfunction "OUT_20") (pintype "passive"))
      (node (ref "U2") (pin "10") (pinfunction "VIN_10") (pintype "passive"))
      (node (ref "U2") (pin "11") (pinfunction "VIN_11") (pintype "passive"))
    )
    (net (code "81") (name "/VSystem_User") (class "Default")
      (node (ref "D8") (pin "CATHODE") (pinfunction "CATHODE_CATHODE") (pintype "passive"))
      (node (ref "JRIGHT") (pin "1") (pinfunction "1_1") (pintype "passive"))
    )
    (net (code "82") (name "/WAKE_USR") (class "Default")
      (node (ref "D7") (pin "ANODE") (pinfunction "ANODE_ANODE") (pintype "passive"))
      (node (ref "U5") (pin "50") (pinfunction "PTC5_50") (pintype "passive"))
      (node (ref "U6") (pin "28") (pinfunction "PTC7_28") (pintype "passive"))
    )
    (net (code "83") (name "GND") (class "Default")
      (node (ref "ANT_UFL") (pin "GND1") (pinfunction "GND1_GND1") (pintype "passive"))
      (node (ref "ANT_UFL") (pin "GND2") (pinfunction "GND2_GND2") (pintype "passive"))
      (node (ref "ANT_UFL") (pin "GND3") (pinfunction "GND3_GND3") (pintype "passive"))
      (node (ref "C1") (pin "2") (pinfunction "2_2") (pintype "passive"))
      (node (ref "C10") (pin "2") (pinfunction "2_2") (pintype "passive"))
      (node (ref "C11") (pin "2") (pinfunction "2_2") (pintype "passive"))
      (node (ref "C12") (pin "2") (pinfunction "2_2") (pintype "passive"))
      (node (ref "C16") (pin "2") (pinfunction "2_2") (pintype "passive"))
      (node (ref "C18") (pin "2") (pinfunction "2_2") (pintype "passive"))
      (node (ref "C2") (pin "2") (pinfunction "2_2") (pintype "passive"))
      (node (ref "C20") (pin "2") (pinfunction "2_2") (pintype "passive"))
      (node (ref "C24") (pin "2") (pinfunction "2_2") (pintype "passive"))
      (node (ref "C25") (pin "2") (pinfunction "2_2") (pintype "passive"))
      (node (ref "C26") (pin "2") (pinfunction "2_2") (pintype "passive"))
      (node (ref "C27") (pin "2") (pinfunction "2_2") (pintype "passive"))
      (node (ref "C28") (pin "2") (pinfunction "2_2") (pintype "passive"))
      (node (ref "C3") (pin "2") (pinfunction "2_2") (pintype "passive"))
      (node (ref "C33") (pin "2") (pinfunction "2_2") (pintype "passive"))
      (node (ref "C34") (pin "2") (pinfunction "2_2") (pintype "passive"))
      (node (ref "C36") (pin "2") (pinfunction "2_2") (pintype "passive"))
      (node (ref "C37") (pin "2") (pinfunction "2_2") (pintype "passive"))
      (node (ref "C38") (pin "2") (pinfunction "2_2") (pintype "passive"))
      (node (ref "C39") (pin "2") (pinfunction "2_2") (pintype "passive"))
      (node (ref "C4") (pin "2") (pinfunction "2_2") (pintype "passive"))
      (node (ref "C40") (pin "2") (pinfunction "2_2") (pintype "passive"))
      (node (ref "C41") (pin "2") (pinfunction "2_2") (pintype "passive"))
      (node (ref "C42") (pin "2") (pinfunction "2_2") (pintype "passive"))
      (node (ref "C43") (pin "2") (pinfunction "2_2") (pintype "passive"))
      (node (ref "C44") (pin "2") (pinfunction "2_2") (pintype "passive"))
      (node (ref "C45") (pin "2") (pinfunction "2_2") (pintype "passive"))
      (node (ref "C46") (pin "2") (pinfunction "2_2") (pintype "passive"))
      (node (ref "C47") (pin "2") (pinfunction "2_2") (pintype "passive"))
      (node (ref "C48") (pin "2") (pinfunction "2_2") (pintype "passive"))
      (node (ref "C49") (pin "2") (pinfunction "2_2") (pintype "passive"))
      (node (ref "C6") (pin "2") (pinfunction "2_2") (pintype "passive"))
      (node (ref "C7") (pin "2") (pinfunction "2_2") (pintype "passive"))
      (node (ref "C8") (pin "2") (pinfunction "2_2") (pintype "passive"))
      (node (ref "C9") (pin "2") (pinfunction "2_2") (pintype "passive"))
      (node (ref "D10") (pin "1") (pinfunction "1_1") (pintype "passive"))
      (node (ref "D11") (pin "1") (pinfunction "1_1") (pintype "passive"))
      (node (ref "D3") (pin "1") (pinfunction "1_1") (pintype "passive"))
      (node (ref "D4") (pin "1") (pinfunction "1_1") (pintype "passive"))
      (node (ref "D5") (pin "1") (pinfunction "1_1") (pintype "passive"))
      (node (ref "D6") (pin "1") (pinfunction "1_1") (pintype "passive"))
      (node (ref "D9") (pin "1") (pinfunction "1_1") (pintype "passive"))
      (node (ref "J1") (pin "GND") (pinfunction "Chassis_GND") (pintype "passive"))
      (node (ref "J20") (pin "CHASSIS1") (pinfunction "CHASSIS_1_CHASSIS1") (pintype "passive"))
      (node (ref "J20") (pin "CHASSIS2") (pinfunction "CHASSIS_2_CHASSIS2") (pintype "passive"))
      (node (ref "J20") (pin "GND") (pinfunction "GND_GND") (pintype "passive"))
      (node (ref "JLEFT") (pin "2") (pinfunction "2_2") (pintype "passive"))
      (node (ref "JRIGHT") (pin "2") (pinfunction "2_2") (pintype "passive"))
      (node (ref "L3") (pin "2") (pinfunction "P$2_2") (pintype "passive"))
      (node (ref "R12") (pin "2") (pinfunction "2_2") (pintype "passive"))
      (node (ref "R2000") (pin "1") (pinfunction "1_1") (pintype "passive"))
      (node (ref "R26") (pin "1") (pinfunction "1_1") (pintype "passive"))
      (node (ref "R52") (pin "1") (pinfunction "1_1") (pintype "passive"))
      (node (ref "R65") (pin "1") (pinfunction "1_1") (pintype "passive"))
      (node (ref "R7") (pin "1") (pinfunction "1_1") (pintype "passive"))
      (node (ref "R8") (pin "1") (pinfunction "1_1") (pintype "passive"))
      (node (ref "SIM1") (pin "C5") (pinfunction "GND_C5") (pintype "passive"))
      (node (ref "SW1") (pin "3") (pinfunction "P$1_3") (pintype "passive"))
      (node (ref "SW1") (pin "4") (pinfunction "P$2_4") (pintype "passive"))
      (node (ref "SW2") (pin "3") (pinfunction "P$1_3") (pintype "passive"))
      (node (ref "SW2") (pin "4") (pinfunction "P$2_4") (pintype "passive"))
      (node (ref "U1") (pin "10") (pinfunction "Vss_10") (pintype "passive"))
      (node (ref "U1") (pin "11") (pinfunction "Vss_11") (pintype "passive"))
      (node (ref "U1") (pin "21") (pinfunction "Vss_21") (pintype "passive"))
      (node (ref "U10") (pin "2") (pinfunction "GND_2") (pintype "passive"))
      (node (ref "U10") (pin "5") (pinfunction "GND_5") (pintype "passive"))
      (node (ref "U16") (pin "1") (pinfunction "GND$1_1") (pintype "passive"))
      (node (ref "U16") (pin "10") (pinfunction "RTS$10_10") (pintype "passive"))
      (node (ref "U16") (pin "14") (pinfunction "GND$14_14") (pintype "passive"))
      (node (ref "U16") (pin "20") (pinfunction "GND$20_20") (pintype "passive"))
      (node (ref "U16") (pin "21") (pinfunction "GND$21_21") (pintype "passive"))
      (node (ref "U16") (pin "22") (pinfunction "GND$22_22") (pintype "power_in"))
      (node (ref "U16") (pin "3") (pinfunction "GND$3_3") (pintype "passive"))
      (node (ref "U16") (pin "30") (pinfunction "GND$30_30") (pintype "passive"))
      (node (ref "U16") (pin "32") (pinfunction "GND$32_32") (pintype "power_in"))
      (node (ref "U16") (pin "33") (pinfunction "RSVD$33_33") (pintype "power_in"))
      (node (ref "U16") (pin "43") (pinfunction "GND$43_43") (pintype "passive"))
      (node (ref "U16") (pin "5") (pinfunction "GND$5_5") (pintype "passive"))
      (node (ref "U16") (pin "50") (pinfunction "GND$50_50") (pintype "passive"))
      (node (ref "U16") (pin "54") (pinfunction "GND$54_54") (pintype "power_in"))
      (node (ref "U16") (pin "55") (pinfunction "GND$55_55") (pintype "power_in"))
      (node (ref "U16") (pin "57") (pinfunction "GND$57_57") (pintype "power_in"))
      (node (ref "U16") (pin "58") (pinfunction "GND$58_58") (pintype "power_in"))
      (node (ref "U16") (pin "59") (pinfunction "GND$59_59") (pintype "power_in"))
      (node (ref "U16") (pin "60") (pinfunction "GND$60_60") (pintype "power_in"))
      (node (ref "U16") (pin "61") (pinfunction "GND$61_61") (pintype "power_in"))
      (node (ref "U16") (pin "63") (pinfunction "GND$63_63") (pintype "power_in"))
      (node (ref "U16") (pin "64") (pinfunction "GND$64_64") (pintype "power_in"))
      (node (ref "U16") (pin "65") (pinfunction "GND$65_65") (pintype "passive"))
      (node (ref "U16") (pin "66") (pinfunction "GND$66_66") (pintype "passive"))
      (node (ref "U16") (pin "67") (pinfunction "GND$67_67") (pintype "passive"))
      (node (ref "U16") (pin "68") (pinfunction "GND$68_68") (pintype "passive"))
      (node (ref "U16") (pin "69") (pinfunction "GND$69_69") (pintype "passive"))
      (node (ref "U16") (pin "70") (pinfunction "GND$70_70") (pintype "passive"))
      (node (ref "U16") (pin "71") (pinfunction "GND$71_71") (pintype "passive"))
      (node (ref "U16") (pin "72") (pinfunction "GND$72_72") (pintype "passive"))
      (node (ref "U16") (pin "73") (pinfunction "GND$73_73") (pintype "passive"))
      (node (ref "U16") (pin "74") (pinfunction "GND$74_74") (pintype "passive"))
      (node (ref "U16") (pin "75") (pinfunction "GND$75_75") (pintype "passive"))
      (node (ref "U16") (pin "76") (pinfunction "GND$76_76") (pintype "passive"))
      (node (ref "U16") (pin "77") (pinfunction "GND$77_77") (pintype "passive"))
      (node (ref "U16") (pin "78") (pinfunction "GND$78_78") (pintype "passive"))
      (node (ref "U16") (pin "79") (pinfunction "GND$79_79") (pintype "passive"))
      (node (ref "U16") (pin "80") (pinfunction "GND$80_80") (pintype "passive"))
      (node (ref "U16") (pin "81") (pinfunction "GND$81_81") (pintype "passive"))
      (node (ref "U16") (pin "82") (pinfunction "GND$82_82") (pintype "passive"))
      (node (ref "U16") (pin "83") (pinfunction "GND$83_83") (pintype "passive"))
      (node (ref "U16") (pin "84") (pinfunction "GND$84_84") (pintype "passive"))
      (node (ref "U16") (pin "85") (pinfunction "GND$85_85") (pintype "passive"))
      (node (ref "U16") (pin "86") (pinfunction "GND$86_86") (pintype "passive"))
      (node (ref "U16") (pin "87") (pinfunction "GND$87_87") (pintype "passive"))
      (node (ref "U16") (pin "88") (pinfunction "GND$88_88") (pintype "passive"))
      (node (ref "U16") (pin "89") (pinfunction "GND$89_89") (pintype "passive"))
      (node (ref "U16") (pin "9") (pinfunction "DTR$9_9") (pintype "passive"))
      (node (ref "U16") (pin "90") (pinfunction "GND$90_90") (pintype "passive"))
      (node (ref "U16") (pin "91") (pinfunction "GND$91_91") (pintype "passive"))
      (node (ref "U16") (pin "92") (pinfunction "GND$92_92") (pintype "passive"))
      (node (ref "U16") (pin "93") (pinfunction "GND$93_93") (pintype "passive"))
      (node (ref "U16") (pin "94") (pinfunction "GND$94_94") (pintype "passive"))
      (node (ref "U16") (pin "95") (pinfunction "GND$95_95") (pintype "passive"))
      (node (ref "U16") (pin "96") (pinfunction "GND$96_96") (pintype "passive"))
      (node (ref "U19") (pin "1") (pinfunction "CTG_1") (pintype "passive"))
      (node (ref "U19") (pin "4") (pinfunction "GND_4") (pintype "passive"))
      (node (ref "U19") (pin "6") (pinfunction "QST_6") (pintype "passive"))
      (node (ref "U19") (pin "EP") (pinfunction "GND_EP") (pintype "passive"))
      (node (ref "U2") (pin "13") (pinfunction "PS/SYNC_13") (pintype "passive"))
      (node (ref "U2") (pin "2") (pinfunction "GND_2") (pintype "passive"))
      (node (ref "U2") (pin "POWERPAD") (pinfunction "PGND_POWERPAD") (pintype "passive"))
      (node (ref "U5") (pin "31") (pinfunction "VSS_31") (pintype "passive"))
      (node (ref "U5") (pin "4") (pinfunction "VSS_4") (pintype "passive"))
      (node (ref "U5") (pin "47") (pinfunction "VSS_47") (pintype "passive"))
      (node (ref "U6") (pin "16") (pinfunction "VSS_16") (pintype "passive"))
      (node (ref "U6") (pin "8") (pinfunction "VSSA_8") (pintype "passive"))
      (node (ref "U6") (pin "PAD") (pinfunction "VSS_PAD") (pintype "passive"))
      (node (ref "U8") (pin "P$1") (pinfunction "A1_P$1") (pintype "passive"))
      (node (ref "U8") (pin "P$11") (pinfunction "B2_P$11") (pintype "passive"))
      (node (ref "U8") (pin "P$16") (pinfunction "DIR2_P$16") (pintype "passive"))
      (node (ref "U8") (pin "P$6") (pinfunction "DIR4_P$6") (pintype "passive"))
      (node (ref "U8") (pin "P$7") (pinfunction "~OE_P$7") (pintype "passive"))
      (node (ref "U8") (pin "P$8") (pinfunction "GND_P$8") (pintype "passive"))
      (node (ref "U9") (pin "2") (pinfunction "GND_2") (pintype "passive"))
      (node (ref "X1") (pin "2") (pinfunction "2_2") (pintype "passive"))
      (node (ref "X1") (pin "4") (pinfunction "2_4") (pintype "passive"))
    )
    (net (code "84") (name "Net-(D1-PadCATHODE)") (class "Default")
      (node (ref "D1") (pin "CATHODE") (pinfunction "CATHODE_CATHODE") (pintype "passive"))
      (node (ref "R26") (pin "2") (pinfunction "2_2") (pintype "passive"))
    )
    (net (code "85") (name "Net-(D2-CATHODE_B)") (class "Default")
      (node (ref "D2") (pin "3") (pinfunction "CATHODE_B_3") (pintype "passive"))
      (node (ref "R21") (pin "2") (pinfunction "2_2") (pintype "passive"))
    )
    (net (code "86") (name "Net-(D2-CATHODE_G)") (class "Default")
      (node (ref "D2") (pin "4") (pinfunction "CATHODE_G_4") (pintype "passive"))
      (node (ref "R22") (pin "2") (pinfunction "2_2") (pintype "passive"))
    )
    (net (code "87") (name "Net-(D2-CATHODE_R)") (class "Default")
      (node (ref "D2") (pin "2") (pinfunction "CATHODE_R_2") (pintype "passive"))
      (node (ref "R20") (pin "2") (pinfunction "2_2") (pintype "passive"))
    )
    (net (code "88") (name "Net-(D7-PadCATHODE)") (class "Default")
      (node (ref "D7") (pin "CATHODE") (pinfunction "CATHODE_CATHODE") (pintype "passive"))
      (node (ref "R65") (pin "2") (pinfunction "2_2") (pintype "passive"))
    )
    (net (code "89") (name "Net-(L1-P$2)") (class "Default")
      (node (ref "C13") (pin "1") (pinfunction "1_1") (pintype "passive"))
      (node (ref "L1") (pin "2") (pinfunction "P$2_2") (pintype "passive"))
      (node (ref "R19") (pin "1") (pinfunction "1_1") (pintype "passive"))
      (node (ref "U5") (pin "13") (pinfunction "VDDA_13") (pintype "passive"))
    )
    (net (code "90") (name "Net-(L2-P$1)") (class "Default")
      (node (ref "L2") (pin "1") (pinfunction "P$1_1") (pintype "passive"))
      (node (ref "U4") (pin "ANODE") (pinfunction "ANODE_ANODE") (pintype "passive"))
    )
    (net (code "91") (name "Net-(L5-PadP$1)") (class "Default")
      (node (ref "L5") (pin "P$1") (pinfunction "P$1_P$1") (pintype "passive"))
      (node (ref "U2") (pin "8") (pinfunction "L1_8") (pintype "passive"))
      (node (ref "U2") (pin "9") (pinfunction "L1_9") (pintype "passive"))
    )
    (net (code "92") (name "Net-(L5-PadP$2)") (class "Default")
      (node (ref "L5") (pin "P$2") (pinfunction "P$2_P$2") (pintype "passive"))
      (node (ref "U2") (pin "6") (pinfunction "L2_6") (pintype "passive"))
      (node (ref "U2") (pin "7") (pinfunction "L2_7") (pintype "passive"))
    )
    (net (code "93") (name "Net-(U1-PROG1)") (class "Default")
      (node (ref "R8") (pin "2") (pinfunction "2_2") (pintype "passive"))
      (node (ref "U1") (pin "13") (pinfunction "PROG1_13") (pintype "passive"))
    )
    (net (code "94") (name "Net-(U1-PROG3)") (class "Default")
      (node (ref "R7") (pin "2") (pinfunction "2_2") (pintype "passive"))
      (node (ref "U1") (pin "12") (pinfunction "PROG3_12") (pintype "passive"))
    )
    (net (code "95") (name "Net-(U1-Therm)") (class "Default")
      (node (ref "R2000") (pin "2") (pinfunction "2_2") (pintype "passive"))
      (node (ref "U1") (pin "5") (pinfunction "Therm_5") (pintype "passive"))
    )
    (net (code "96") (name "Net-(U2-EN)") (class "Default")
      (node (ref "C48") (pin "1") (pinfunction "1_1") (pintype "passive"))
      (node (ref "U2") (pin "1") (pinfunction "VINA_1") (pintype "passive"))
      (node (ref "U2") (pin "12") (pinfunction "EN_12") (pintype "passive"))
    )
    (net (code "97") (name "Net-(U2-FB)") (class "Default")
      (node (ref "R12") (pin "1") (pinfunction "1_1") (pintype "passive"))
      (node (ref "R13") (pin "1") (pinfunction "1_1") (pintype "passive"))
      (node (ref "U2") (pin "3") (pinfunction "FB_3") (pintype "passive"))
    )
    (net (code "98") (name "Net-(U5-EXTAL32)") (class "Default")
      (node (ref "U5") (pin "20") (pinfunction "EXTAL32_20") (pintype "passive"))
      (node (ref "X2") (pin "1") (pinfunction "XTAL1_1") (pintype "passive"))
    )
    (net (code "99") (name "Net-(U5-PTA18)") (class "Default")
      (node (ref "U5") (pin "32") (pinfunction "PTA18_32") (pintype "passive"))
      (node (ref "X1") (pin "1") (pinfunction "1_1") (pintype "passive"))
    )
    (net (code "100") (name "Net-(U5-PTA19)") (class "Default")
      (node (ref "U5") (pin "33") (pinfunction "PTA19_33") (pintype "passive"))
      (node (ref "X1") (pin "3") (pinfunction "3_3") (pintype "passive"))
    )
    (net (code "101") (name "Net-(U5-VREF_OUT)") (class "Default")
      (node (ref "C15") (pin "1") (pinfunction "1_1") (pintype "passive"))
      (node (ref "U5") (pin "17") (pinfunction "VREF_OUT_17") (pintype "passive"))
    )
    (net (code "102") (name "Net-(U5-XTAL32)") (class "Default")
      (node (ref "U5") (pin "19") (pinfunction "XTAL32_19") (pintype "passive"))
      (node (ref "X2") (pin "2") (pinfunction "XTAL2_2") (pintype "passive"))
    )
    (net (code "103") (name "Net-(U6-PTA18)") (class "Default")
      (node (ref "U6") (pin "17") (pinfunction "PTA18_17") (pintype "passive"))
      (node (ref "X3") (pin "2") (pinfunction "XTAL2_2") (pintype "passive"))
    )
    (net (code "104") (name "Net-(U6-PTA19)") (class "Default")
      (node (ref "U6") (pin "18") (pinfunction "PTA19_18") (pintype "passive"))
      (node (ref "X3") (pin "1") (pinfunction "XTAL1_1") (pintype "passive"))
    )
    (net (code "105") (name "Net-(U19-CELL)") (class "Default")
      (node (ref "C20") (pin "1") (pinfunction "1_1") (pintype "passive"))
      (node (ref "R45") (pin "1") (pinfunction "1_1") (pintype "passive"))
      (node (ref "U19") (pin "2") (pinfunction "CELL_2") (pintype "passive"))
    )
    (net (code "106") (name "unconnected-(SIM1-NC1-PadMTG1)") (class "Default")
      (node (ref "SIM1") (pin "MTG1") (pinfunction "NC1_MTG1") (pintype "passive"))
    )
    (net (code "107") (name "unconnected-(SIM1-NC2-PadMTG2)") (class "Default")
      (node (ref "SIM1") (pin "MTG2") (pinfunction "NC2_MTG2") (pintype "passive"))
    )
    (net (code "108") (name "unconnected-(U2-PG-Pad14)") (class "Default")
      (node (ref "U2") (pin "14") (pinfunction "PG_14") (pintype "passive"))
    )
    (net (code "109") (name "unconnected-(U5-PGA0_DM-Pad10)") (class "Default")
      (node (ref "U5") (pin "10") (pinfunction "PGA0_DM_10") (pintype "passive"))
    )
    (net (code "110") (name "unconnected-(U5-PGA0_DP-Pad9)") (class "Default")
      (node (ref "U5") (pin "9") (pinfunction "PGA0_DP_9") (pintype "passive"))
    )
    (net (code "111") (name "unconnected-(U5-PGA1_DM-Pad12)") (class "Default")
      (node (ref "U5") (pin "12") (pinfunction "PGA1_DM_12") (pintype "passive"))
    )
    (net (code "112") (name "unconnected-(U5-PGA1_DP-Pad11)") (class "Default")
      (node (ref "U5") (pin "11") (pinfunction "PGA1_DP_11") (pintype "passive"))
    )
    (net (code "113") (name "unconnected-(U5-PTB16-Pad39)") (class "Default")
      (node (ref "U5") (pin "39") (pinfunction "PTB16_39") (pintype "passive"))
    )
    (net (code "114") (name "unconnected-(U5-PTB17-Pad40)") (class "Default")
      (node (ref "U5") (pin "40") (pinfunction "PTB17_40") (pintype "passive"))
    )
    (net (code "115") (name "unconnected-(U8-A2-PadP$2)") (class "Default")
      (node (ref "U8") (pin "P$2") (pinfunction "A2_P$2") (pintype "passive+no_connect"))
    )
    (net (code "116") (name "unconnected-(U8-B1-PadP$12)") (class "Default")
      (node (ref "U8") (pin "P$12") (pinfunction "B1_P$12") (pintype "passive+no_connect"))
    )
    (net (code "117") (name "unconnected-(U9-OC-Pad3)") (class "Default")
      (node (ref "U9") (pin "3") (pinfunction "OC_3") (pintype "passive+no_connect"))
    )
    (net (code "118") (name "unconnected-(U16-ANT_DET$62-Pad62)") (class "Default")
      (node (ref "U16") (pin "62") (pinfunction "ANT_DET$62_62") (pintype "power_in"))
    )
    (net (code "119") (name "unconnected-(U16-CODEC_CLK$19-Pad19)") (class "Default")
      (node (ref "U16") (pin "19") (pinfunction "CODEC_CLK$19_19") (pintype "passive"))
    )
    (net (code "120") (name "unconnected-(U16-CTS$11-Pad11)") (class "Default")
      (node (ref "U16") (pin "11") (pinfunction "CTS$11_11") (pintype "passive+no_connect"))
    )
    (net (code "121") (name "unconnected-(U16-DCD$8-Pad8)") (class "Default")
      (node (ref "U16") (pin "8") (pinfunction "DCD$8_8") (pintype "passive"))
    )
    (net (code "122") (name "unconnected-(U16-DSR$6-Pad6)") (class "Default")
      (node (ref "U16") (pin "6") (pinfunction "DSR$6_6") (pintype "passive"))
    )
    (net (code "123") (name "unconnected-(U16-GPIO2$23-Pad23)") (class "Default")
      (node (ref "U16") (pin "23") (pinfunction "GPIO2$23_23") (pintype "power_in"))
    )
    (net (code "124") (name "unconnected-(U16-GPIO3$24-Pad24)") (class "Default")
      (node (ref "U16") (pin "24") (pinfunction "GPIO3$24_24") (pintype "passive"))
    )
    (net (code "125") (name "unconnected-(U16-GPIO4$25-Pad25)") (class "Default")
      (node (ref "U16") (pin "25") (pinfunction "GPIO4$25_25") (pintype "power_in"))
    )
    (net (code "126") (name "unconnected-(U16-I2S_CLK$36-Pad36)") (class "Default")
      (node (ref "U16") (pin "36") (pinfunction "I2S_CLK$36_36") (pintype "passive"))
    )
    (net (code "127") (name "unconnected-(U16-I2S_RXD$37-Pad37)") (class "Default")
      (node (ref "U16") (pin "37") (pinfunction "I2S_RXD$37_37") (pintype "passive"))
    )
    (net (code "128") (name "unconnected-(U16-I2S_TXD$35-Pad35)") (class "Default")
      (node (ref "U16") (pin "35") (pinfunction "I2S_TXD$35_35") (pintype "power_in"))
    )
    (net (code "129") (name "unconnected-(U16-I2S_WA$34-Pad34)") (class "Default")
      (node (ref "U16") (pin "34") (pinfunction "I2S_WA$34_34") (pintype "power_in"))
    )
    (net (code "130") (name "unconnected-(U16-RI$7-Pad7)") (class "Default")
      (node (ref "U16") (pin "7") (pinfunction "RI$7_7") (pintype "passive"))
    )
    (net (code "131") (name "unconnected-(U16-RSVD$31-Pad31)") (class "Default")
      (node (ref "U16") (pin "31") (pinfunction "RSVD$31_31") (pintype "power_in"))
    )
    (net (code "132") (name "unconnected-(U16-RSVD$44-Pad44)") (class "Default")
      (node (ref "U16") (pin "44") (pinfunction "RSVD$44_44") (pintype "passive"))
    )
    (net (code "133") (name "unconnected-(U16-RSVD$45-Pad45)") (class "Default")
      (node (ref "U16") (pin "45") (pinfunction "RSVD$45_45") (pintype "passive"))
    )
    (net (code "134") (name "unconnected-(U16-RSVD$46-Pad46)") (class "Default")
      (node (ref "U16") (pin "46") (pinfunction "RSVD$46_46") (pintype "passive"))
    )
    (net (code "135") (name "unconnected-(U16-RSVD$47-Pad47)") (class "Default")
      (node (ref "U16") (pin "47") (pinfunction "RSVD$47_47") (pintype "passive"))
    )
    (net (code "136") (name "unconnected-(U16-RSVD$48-Pad48)") (class "Default")
      (node (ref "U16") (pin "48") (pinfunction "RSVD$48_48") (pintype "passive"))
    )
    (net (code "137") (name "unconnected-(U16-RSVD$49-Pad49)") (class "Default")
      (node (ref "U16") (pin "49") (pinfunction "RSVD$49_49") (pintype "passive"))
    )
    (net (code "138") (name "unconnected-(U16-SCL$27-Pad27)") (class "Default")
      (node (ref "U16") (pin "27") (pinfunction "SCL$27_27") (pintype "power_in"))
    )
    (net (code "139") (name "unconnected-(U16-SDA$26-Pad26)") (class "Default")
      (node (ref "U16") (pin "26") (pinfunction "SDA$26_26") (pintype "power_in"))
    )
    (net (code "140") (name "unconnected-(U16-SIM_DET$42-Pad42)") (class "Default")
      (node (ref "U16") (pin "42") (pinfunction "SIM_DET$42_42") (pintype "passive"))
    )
    (net (code "141") (name "unconnected-(U16-V_USB_DET$17-Pad17)") (class "Default")
      (node (ref "U16") (pin "17") (pinfunction "V_USB_DET$17_17") (pintype "passive"))
    )
    (net (code "142") (name "unconnected-(U19-ALT-Pad5)") (class "Default")
      (node (ref "U19") (pin "5") (pinfunction "ALT_5") (pintype "passive"))
    )
  )
)
